# Seeeduino_GPRS_v1_0.net
KiCad netlist of a schematic drawn in EAGLE
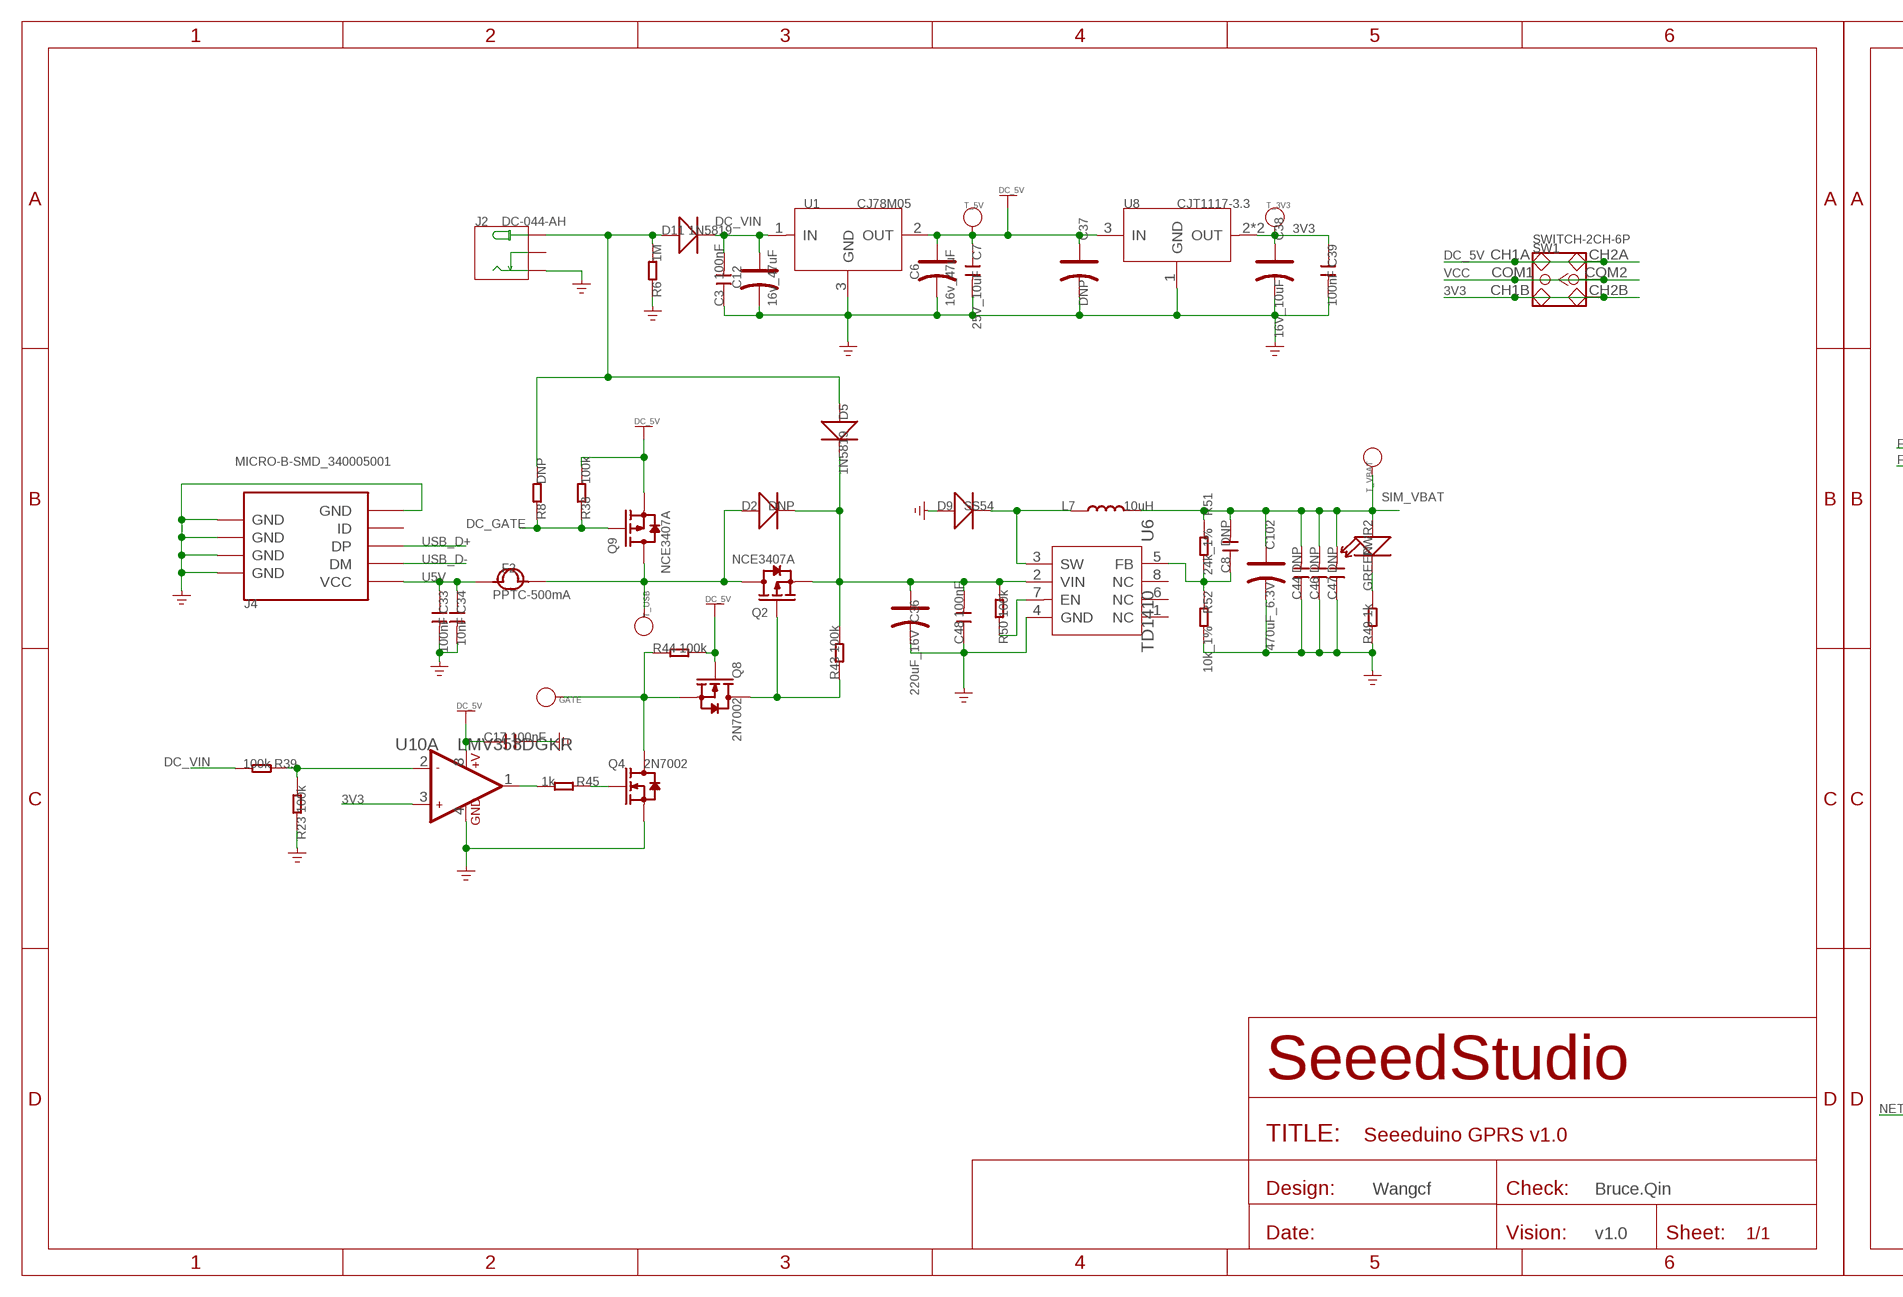
[diagram p0: schematic, sheet 1, part 1 of 3]
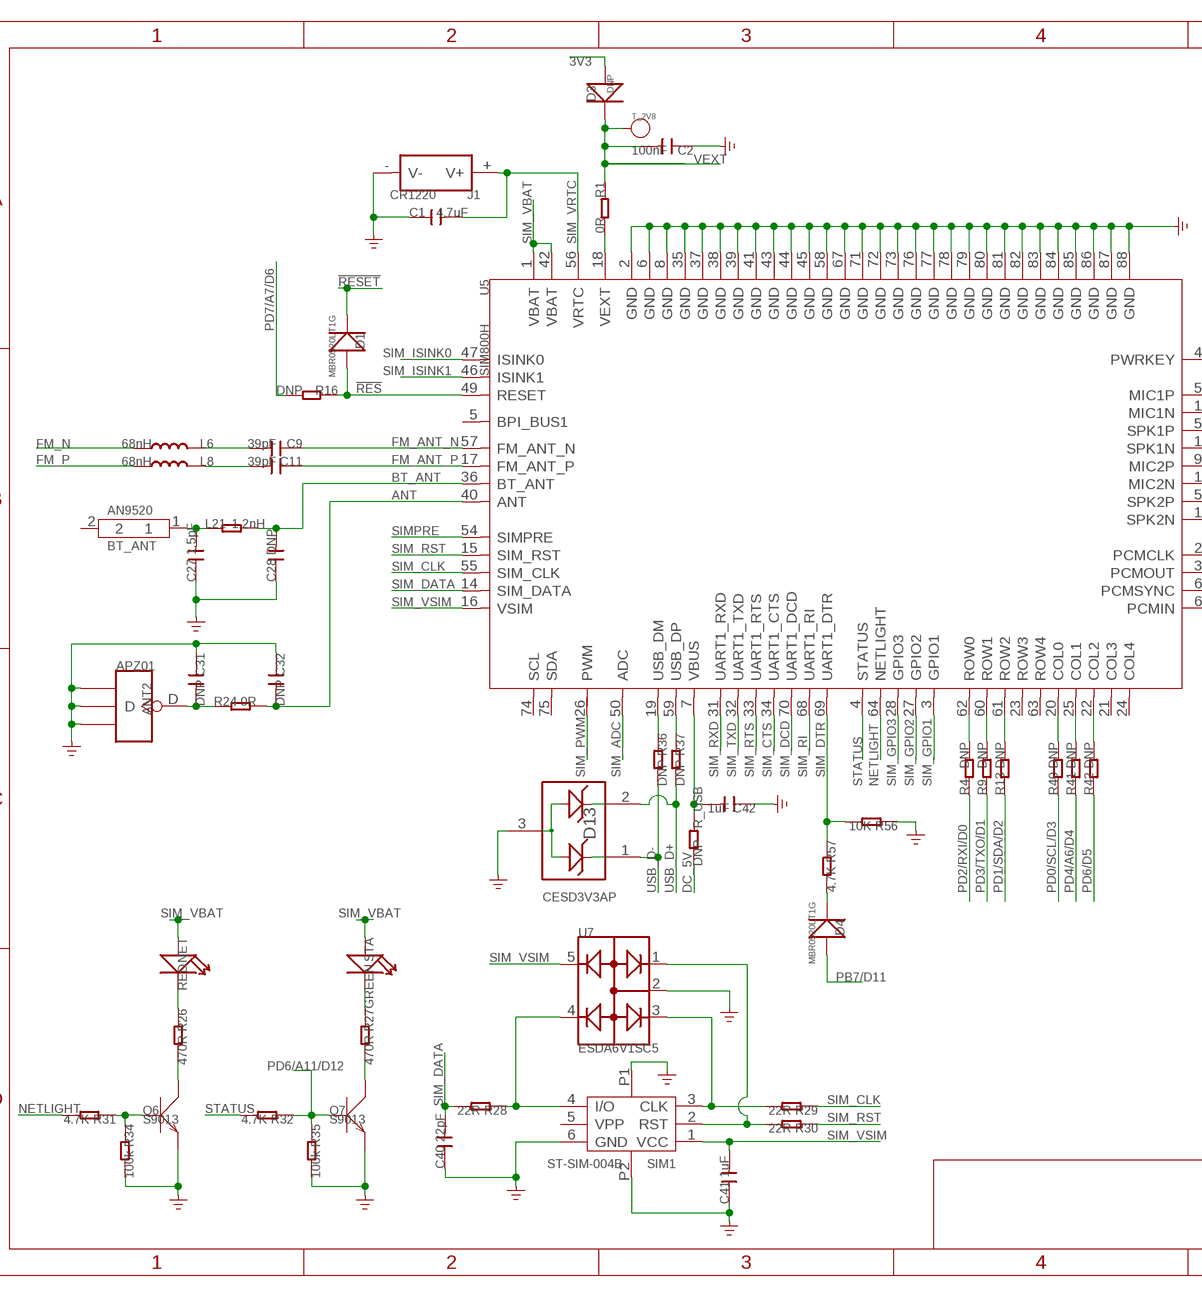
[diagram p1: schematic, sheet 1, part 2 of 3]
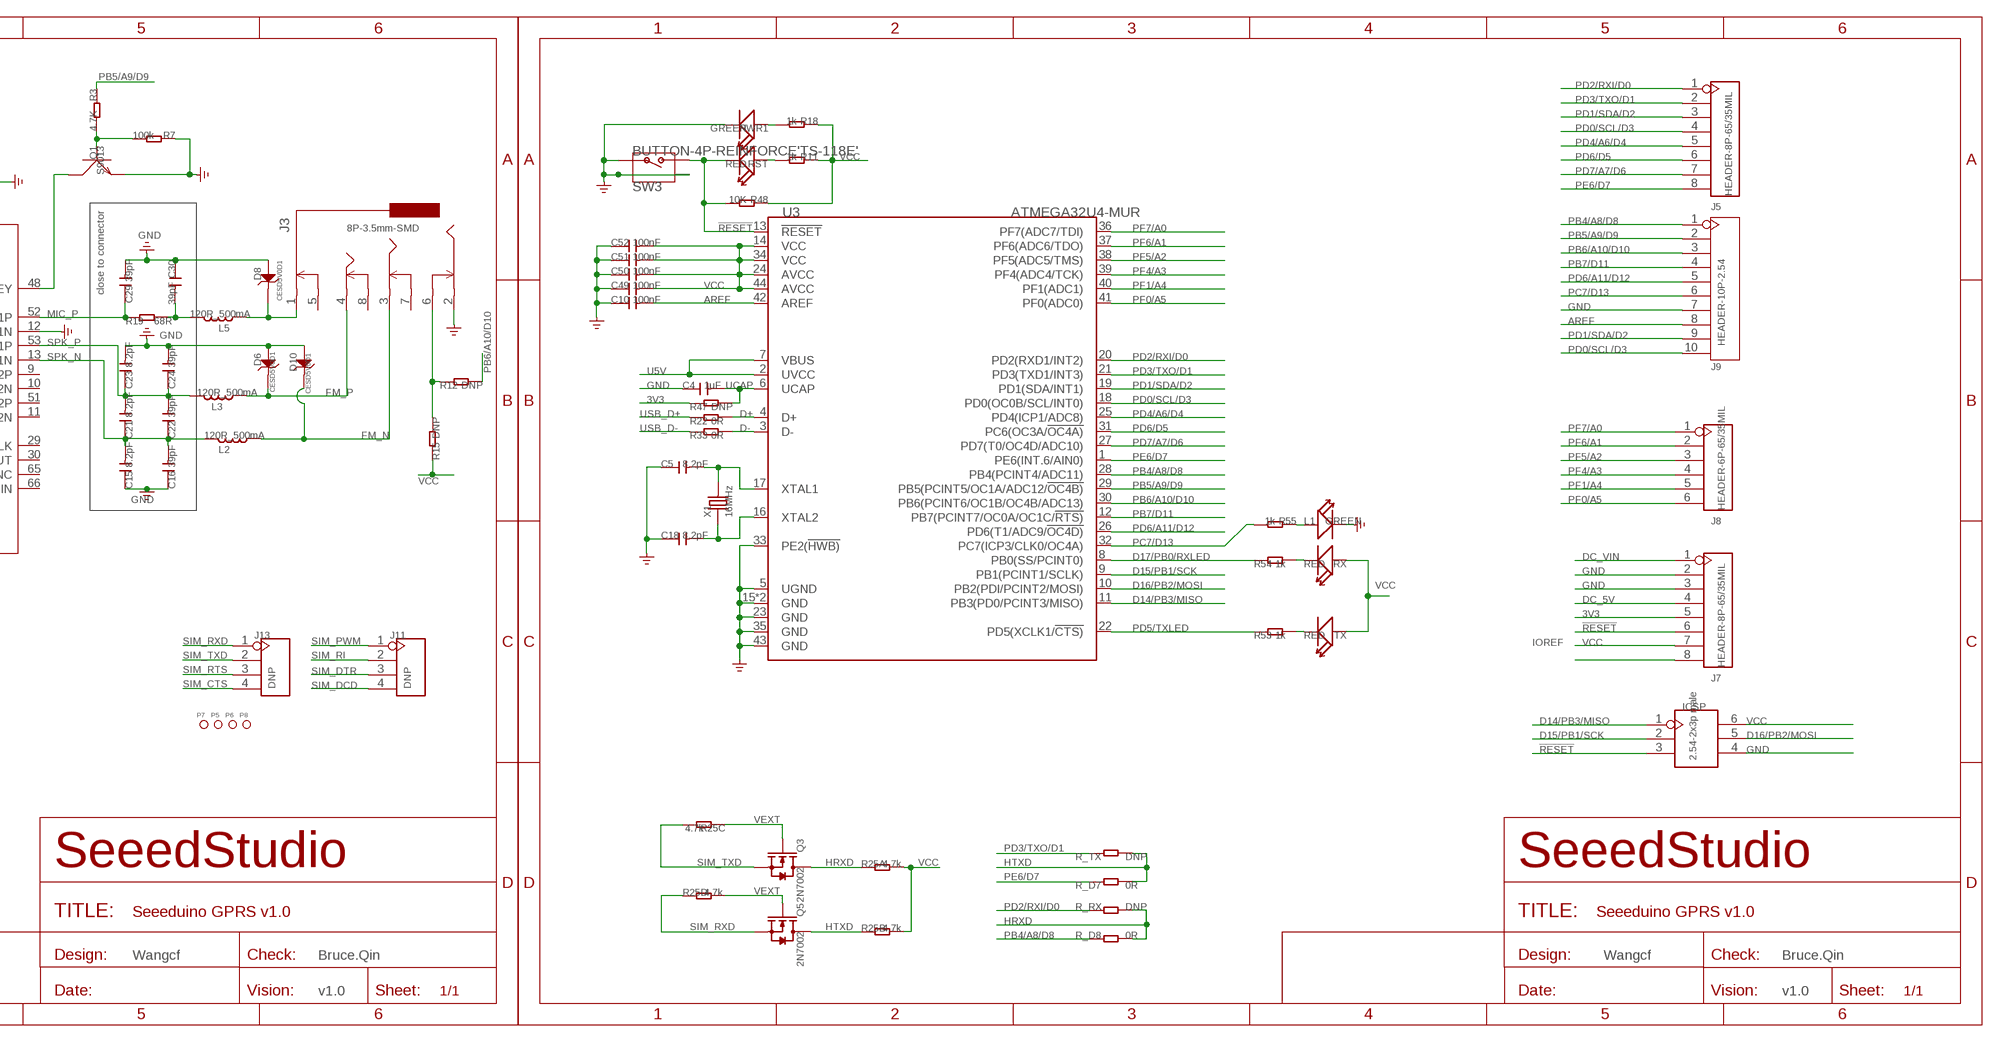
[diagram p2: schematic, sheet 1, part 3 of 3]

(export (version "E")
  (design (tool "Eeschema 10.0.6"))
  (components
    (comp (ref "ANT2")
      (value "APZ01")
      (footprint "eagle-import:4P-U-FL")
      (libsource (lib "eagle-import") (part "ANTENNA-U-FL"))
    )
    (comp (ref "BT_ANT")
      (value "AN9520")
      (footprint "eagle-import:2P-9.5X2.1X1MM")
      (libsource (lib "eagle-import") (part "ANTENNA-CERAMICS'AN9520'"))
    )
    (comp (ref "C1")
      (value "4.7uF")
      (footprint "eagle-import:C0805")
      (libsource (lib "eagle-import") (part "C-0805"))
    )
    (comp (ref "C2")
      (value "100nF")
      (footprint "eagle-import:C0603")
      (libsource (lib "eagle-import") (part "C-0603"))
    )
    (comp (ref "C3")
      (value "100nF")
      (footprint "eagle-import:C0603")
      (libsource (lib "eagle-import") (part "C-0603"))
    )
    (comp (ref "C4")
      (value "1uF")
      (footprint "eagle-import:C0603")
      (libsource (lib "eagle-import") (part "C-0603"))
    )
    (comp (ref "C5")
      (value "8.2pF")
      (footprint "eagle-import:C0603")
      (libsource (lib "eagle-import") (part "C-0603"))
    )
    (comp (ref "C6")
      (value "16v_47uF")
      (footprint "eagle-import:AVX-C")
      (libsource (lib "eagle-import") (part "CAP-AVX-C"))
    )
    (comp (ref "C7")
      (value "25V_10uF")
      (footprint "eagle-import:C0805")
      (libsource (lib "eagle-import") (part "C-0805"))
    )
    (comp (ref "C8")
      (value "DNP")
      (footprint "eagle-import:C0603")
      (libsource (lib "eagle-import") (part "C-0603"))
    )
    (comp (ref "C9")
      (value "39pF")
      (footprint "eagle-import:C0603")
      (libsource (lib "eagle-import") (part "C-0603"))
    )
    (comp (ref "C10")
      (value "100nF")
      (footprint "eagle-import:C0603")
      (libsource (lib "eagle-import") (part "C-0603"))
    )
    (comp (ref "C11")
      (value "39pF")
      (footprint "eagle-import:C0603")
      (libsource (lib "eagle-import") (part "C-0603"))
    )
    (comp (ref "C12")
      (value "16v_47uF")
      (footprint "eagle-import:AVX-C")
      (libsource (lib "eagle-import") (part "CAP-AVX-C"))
    )
    (comp (ref "C15")
      (value "8.2pF")
      (footprint "eagle-import:C0603")
      (libsource (lib "eagle-import") (part "C-0603"))
    )
    (comp (ref "C16")
      (value "39pF")
      (footprint "eagle-import:C0603")
      (libsource (lib "eagle-import") (part "C-0603"))
    )
    (comp (ref "C17")
      (value "100nF")
      (footprint "eagle-import:C0603")
      (libsource (lib "eagle-import") (part "C-0603"))
    )
    (comp (ref "C18")
      (value "8.2pF")
      (footprint "eagle-import:C0603")
      (libsource (lib "eagle-import") (part "C-0603"))
    )
    (comp (ref "C21")
      (value "8.2pF")
      (footprint "eagle-import:C0603")
      (libsource (lib "eagle-import") (part "C-0603"))
    )
    (comp (ref "C22")
      (value "39pF")
      (footprint "eagle-import:C0603")
      (libsource (lib "eagle-import") (part "C-0603"))
    )
    (comp (ref "C23")
      (value "8.2pF")
      (footprint "eagle-import:C0603")
      (libsource (lib "eagle-import") (part "C-0603"))
    )
    (comp (ref "C24")
      (value "39pF")
      (footprint "eagle-import:C0603")
      (libsource (lib "eagle-import") (part "C-0603"))
    )
    (comp (ref "C27")
      (value "1.5pF")
      (footprint "eagle-import:C0603")
      (libsource (lib "eagle-import") (part "C-0603"))
    )
    (comp (ref "C28")
      (value "DNP")
      (footprint "eagle-import:C0603")
      (libsource (lib "eagle-import") (part "C-0603"))
    )
    (comp (ref "C29")
      (value "39pF")
      (footprint "eagle-import:C0603")
      (libsource (lib "eagle-import") (part "C-0603"))
    )
    (comp (ref "C30")
      (value "39pF")
      (footprint "eagle-import:C0603")
      (libsource (lib "eagle-import") (part "C-0603"))
    )
    (comp (ref "C31")
      (value "DNP")
      (footprint "eagle-import:C0603")
      (libsource (lib "eagle-import") (part "C-0603"))
    )
    (comp (ref "C32")
      (value "DNP")
      (footprint "eagle-import:C0603")
      (libsource (lib "eagle-import") (part "C-0603"))
    )
    (comp (ref "C33")
      (value "100nF")
      (footprint "eagle-import:C0603")
      (libsource (lib "eagle-import") (part "C-0603"))
    )
    (comp (ref "C34")
      (value "10nF")
      (footprint "eagle-import:C0603")
      (libsource (lib "eagle-import") (part "C-0603"))
    )
    (comp (ref "C36")
      (value "220uF_16V")
      (footprint "eagle-import:ELECTRO-SMD-D-5.6MM")
      (libsource (lib "eagle-import") (part "CAP-ELECTRO-D"))
    )
    (comp (ref "C37")
      (value "DNP")
      (footprint "eagle-import:AVX-A")
      (libsource (lib "eagle-import") (part "CAP-AVX-A"))
    )
    (comp (ref "C38")
      (value "16V_10uF")
      (footprint "eagle-import:AVX-A")
      (libsource (lib "eagle-import") (part "CAP-AVX-A"))
    )
    (comp (ref "C39")
      (value "100nF")
      (footprint "eagle-import:C0603")
      (libsource (lib "eagle-import") (part "C-0603"))
    )
    (comp (ref "C40")
      (value "22pF")
      (footprint "eagle-import:C0603")
      (libsource (lib "eagle-import") (part "C-0603"))
    )
    (comp (ref "C41")
      (value "1uF")
      (footprint "eagle-import:C0603")
      (libsource (lib "eagle-import") (part "C-0603"))
    )
    (comp (ref "C42")
      (value "1uF")
      (footprint "eagle-import:C0603")
      (libsource (lib "eagle-import") (part "C-0603"))
    )
    (comp (ref "C44")
      (value "DNP")
      (footprint "eagle-import:C0603")
      (libsource (lib "eagle-import") (part "C-0603"))
    )
    (comp (ref "C46")
      (value "DNP")
      (footprint "eagle-import:C0603")
      (libsource (lib "eagle-import") (part "C-0603"))
    )
    (comp (ref "C47")
      (value "DNP")
      (footprint "eagle-import:C0603")
      (libsource (lib "eagle-import") (part "C-0603"))
    )
    (comp (ref "C48")
      (value "100nF")
      (footprint "eagle-import:C0603")
      (libsource (lib "eagle-import") (part "C-0603"))
    )
    (comp (ref "C49")
      (value "100nF")
      (footprint "eagle-import:C0603")
      (libsource (lib "eagle-import") (part "C-0603"))
    )
    (comp (ref "C50")
      (value "100nF")
      (footprint "eagle-import:C0603")
      (libsource (lib "eagle-import") (part "C-0603"))
    )
    (comp (ref "C51")
      (value "100nF")
      (footprint "eagle-import:C0603")
      (libsource (lib "eagle-import") (part "C-0603"))
    )
    (comp (ref "C52")
      (value "100nF")
      (footprint "eagle-import:C0603")
      (libsource (lib "eagle-import") (part "C-0603"))
    )
    (comp (ref "C102")
      (value "470uF_6.3V")
      (footprint "eagle-import:AVX-D")
      (libsource (lib "eagle-import") (part "CAP-AVX-D"))
    )
    (comp (ref "D1")
      (value "MBR0520LT1G")
      (footprint "eagle-import:SOD123")
      (libsource (lib "eagle-import") (part "D'1206'"))
    )
    (comp (ref "D2")
      (value "DNP")
      (footprint "eagle-import:SMA")
      (libsource (lib "eagle-import") (part "D'B130L-13-F'"))
    )
    (comp (ref "D3")
      (value "DNP")
      (footprint "eagle-import:SOD123")
      (libsource (lib "eagle-import") (part "D'1206'"))
    )
    (comp (ref "D4")
      (value "MBR0520LT1G")
      (footprint "eagle-import:SOD123")
      (libsource (lib "eagle-import") (part "D'1206'"))
    )
    (comp (ref "D5")
      (value "1N5819")
      (footprint "eagle-import:SMA")
      (libsource (lib "eagle-import") (part "D'B130L-13-F'"))
    )
    (comp (ref "D6")
      (value "CESD5V0D1")
      (footprint "eagle-import:SOD123-2.7X1.6")
      (libsource (lib "eagle-import") (part "D-ESD"))
    )
    (comp (ref "D8")
      (value "CESD5V0D1")
      (footprint "eagle-import:SOD123-2.7X1.6")
      (libsource (lib "eagle-import") (part "D-ESD"))
    )
    (comp (ref "D9")
      (value "SS54")
      (footprint "eagle-import:SMB")
      (libsource (lib "eagle-import") (part "D'MBRS240LT3'"))
    )
    (comp (ref "D10")
      (value "CESD5V0D1")
      (footprint "eagle-import:SOD123-2.7X1.6")
      (libsource (lib "eagle-import") (part "D-ESD"))
    )
    (comp (ref "D11")
      (value "1N5819")
      (footprint "eagle-import:SMA")
      (libsource (lib "eagle-import") (part "D'B130L-13-F'"))
    )
    (comp (ref "D13")
      (value "CESD3V3AP")
      (footprint "eagle-import:SOT23")
      (libsource (lib "eagle-import") (part "D-ESD-3P"))
    )
    (comp (ref "F2")
      (value "PPTC-500mA")
      (footprint "eagle-import:1206")
      (libsource (lib "eagle-import") (part "FUSE"))
    )
    (comp (ref "GATE")
      (value "DNP")
      (footprint "eagle-import:TP_4545")
      (libsource (lib "eagle-import") (part "PAD-TEST-POINT-CIRCLE'4545'"))
    )
    (comp (ref "ICSP")
      (value "2.54-2x3p male")
      (footprint "eagle-import:2X3P-2.54")
      (libsource (lib "eagle-import") (part "HEADER-2X3P-2.54"))
    )
    (comp (ref "J1")
      (value "CR1220")
      (footprint "eagle-import:SMD-CR1220-2")
      (libsource (lib "eagle-import") (part "HOLDER-BAT"))
    )
    (comp (ref "J2")
      (value "DC-044-AH")
      (footprint "eagle-import:DC-404")
      (libsource (lib "eagle-import") (part "DC-044"))
    )
    (comp (ref "J3")
      (value "8P-3.5mm-SMD")
      (footprint "eagle-import:8P-3.5-SMD")
      (libsource (lib "eagle-import") (part "AUDIO-8P'PJ-3536-L6S'"))
    )
    (comp (ref "J4")
      (value "MICRO-B-SMD_340005001")
      (footprint "eagle-import:MICRO-USB")
      (libsource (lib "eagle-import") (part "USB-MINIUSB-5P-MICRO"))
    )
    (comp (ref "J5")
      (value "HEADER-8P-65/35MIL")
      (footprint "eagle-import:8P-2.54-65_35MIL")
      (libsource (lib "eagle-import") (part "HEADER-8P-65/35MIL"))
    )
    (comp (ref "J7")
      (value "HEADER-8P-65/35MIL")
      (footprint "eagle-import:8P-2.54-65_35MIL")
      (libsource (lib "eagle-import") (part "HEADER-8P-65/35MIL"))
    )
    (comp (ref "J8")
      (value "HEADER-6P-65/35MIL")
      (footprint "eagle-import:6P-2.54-65_35MIL")
      (libsource (lib "eagle-import") (part "HEADER-6P-65/35MIL"))
    )
    (comp (ref "J9")
      (value "HEADER-10P-2.54")
      (footprint "eagle-import:10P-2.54")
      (libsource (lib "eagle-import") (part "HEADER-10P-2.54"))
    )
    (comp (ref "J11")
      (value "DNP")
      (footprint "eagle-import:4P-65_35MIL")
      (libsource (lib "eagle-import") (part "HEADER-4P-65/35MIL"))
    )
    (comp (ref "J13")
      (value "DNP")
      (footprint "eagle-import:4P-65_35MIL")
      (libsource (lib "eagle-import") (part "HEADER-4P-65/35MIL"))
    )
    (comp (ref "L1")
      (value "GREEN")
      (footprint "eagle-import:LED-0603")
      (libsource (lib "eagle-import") (part "LED'0603'"))
    )
    (comp (ref "L2")
      (value "120R_500mA")
      (footprint "eagle-import:L0603")
      (libsource (lib "eagle-import") (part "L'0603'"))
    )
    (comp (ref "L3")
      (value "120R_500mA")
      (footprint "eagle-import:L0603")
      (libsource (lib "eagle-import") (part "L'0603'"))
    )
    (comp (ref "L5")
      (value "120R_500mA")
      (footprint "eagle-import:L0603")
      (libsource (lib "eagle-import") (part "L'0603'"))
    )
    (comp (ref "L6")
      (value "68nH")
      (footprint "eagle-import:L0603")
      (libsource (lib "eagle-import") (part "L'0603'"))
    )
    (comp (ref "L7")
      (value "10uH")
      (footprint "eagle-import:L0630")
      (libsource (lib "eagle-import") (part "L'0630'"))
    )
    (comp (ref "L8")
      (value "68nH")
      (footprint "eagle-import:L0603")
      (libsource (lib "eagle-import") (part "L'0603'"))
    )
    (comp (ref "L21")
      (value "1.2nH")
      (footprint "eagle-import:R0603")
      (libsource (lib "eagle-import") (part "R-0603"))
    )
    (comp (ref "NET")
      (value "RED")
      (footprint "eagle-import:LED-0603")
      (libsource (lib "eagle-import") (part "LED'0603'"))
    )
    (comp (ref "P5")
      (value "DNP")
      (footprint "eagle-import:ROUND-MARK-1.0")
      (libsource (lib "eagle-import") (part "PAD-MARK"))
    )
    (comp (ref "P6")
      (value "DNP")
      (footprint "eagle-import:ROUND-MARK-1.0")
      (libsource (lib "eagle-import") (part "PAD-MARK"))
    )
    (comp (ref "P7")
      (value "DNP")
      (footprint "eagle-import:ROUND-MARK-1.0")
      (libsource (lib "eagle-import") (part "PAD-MARK"))
    )
    (comp (ref "P8")
      (value "DNP")
      (footprint "eagle-import:ROUND-MARK-1.0")
      (libsource (lib "eagle-import") (part "PAD-MARK"))
    )
    (comp (ref "PWR1")
      (value "GREEN")
      (footprint "eagle-import:LED-0603")
      (libsource (lib "eagle-import") (part "LED'0603'"))
    )
    (comp (ref "PWR2")
      (value "GREEN")
      (footprint "eagle-import:LED-0603")
      (libsource (lib "eagle-import") (part "LED'0603'"))
    )
    (comp (ref "Q1")
      (value "S9013")
      (footprint "eagle-import:SOT23")
      (libsource (lib "eagle-import") (part "TRANSISTOR-NPN-SOT23"))
    )
    (comp (ref "Q2")
      (value "NCE3407A")
      (footprint "eagle-import:SOT23")
      (libsource (lib "eagle-import") (part "MOSFET-P'SI2323CDS/SI2305DS{lt}BR{gt}'"))
    )
    (comp (ref "Q3")
      (value "2N7002")
      (footprint "eagle-import:SOT23")
      (libsource (lib "eagle-import") (part "MOSFET-N'SOT23'"))
    )
    (comp (ref "Q4")
      (value "2N7002")
      (footprint "eagle-import:SOT23")
      (libsource (lib "eagle-import") (part "MOSFET-N'SOT23'"))
    )
    (comp (ref "Q5")
      (value "2N7002")
      (footprint "eagle-import:SOT23")
      (libsource (lib "eagle-import") (part "MOSFET-N'SOT23'"))
    )
    (comp (ref "Q6")
      (value "S9013")
      (footprint "eagle-import:SOT23")
      (libsource (lib "eagle-import") (part "TRANSISTOR-NPN-SOT23"))
    )
    (comp (ref "Q7")
      (value "S9013")
      (footprint "eagle-import:SOT23")
      (libsource (lib "eagle-import") (part "TRANSISTOR-NPN-SOT23"))
    )
    (comp (ref "Q8")
      (value "2N7002")
      (footprint "eagle-import:SOT23")
      (libsource (lib "eagle-import") (part "MOSFET-N'SOT23'"))
    )
    (comp (ref "Q9")
      (value "NCE3407A")
      (footprint "eagle-import:SOT23")
      (libsource (lib "eagle-import") (part "MOSFET-P'SI2323CDS/SI2305DS{lt}BR{gt}'"))
    )
    (comp (ref "R1")
      (value "0R")
      (footprint "eagle-import:R0603")
      (libsource (lib "eagle-import") (part "R-0603"))
    )
    (comp (ref "R3")
      (value "4.7K")
      (footprint "eagle-import:R0603")
      (libsource (lib "eagle-import") (part "R-0603"))
    )
    (comp (ref "R4")
      (value "DNP")
      (footprint "eagle-import:R0603")
      (libsource (lib "eagle-import") (part "R-0603"))
    )
    (comp (ref "R6")
      (value "1M")
      (footprint "eagle-import:R0603")
      (libsource (lib "eagle-import") (part "R-0603"))
    )
    (comp (ref "R7")
      (value "100k")
      (footprint "eagle-import:R0603")
      (libsource (lib "eagle-import") (part "R-0603"))
    )
    (comp (ref "R8")
      (value "DNP")
      (footprint "eagle-import:R0603")
      (libsource (lib "eagle-import") (part "R-0603"))
    )
    (comp (ref "R9")
      (value "DNP")
      (footprint "eagle-import:R0603")
      (libsource (lib "eagle-import") (part "R-0603"))
    )
    (comp (ref "R11")
      (value "1k")
      (footprint "eagle-import:R0603")
      (libsource (lib "eagle-import") (part "R-0603"))
    )
    (comp (ref "R12")
      (value "DNP")
      (footprint "eagle-import:R0603")
      (libsource (lib "eagle-import") (part "R-0603"))
    )
    (comp (ref "R13")
      (value "DNP")
      (footprint "eagle-import:R0603")
      (libsource (lib "eagle-import") (part "R-0603"))
    )
    (comp (ref "R15")
      (value "DNP")
      (footprint "eagle-import:R0603")
      (libsource (lib "eagle-import") (part "R-0603"))
    )
    (comp (ref "R16")
      (value "DNP")
      (footprint "eagle-import:R0603")
      (libsource (lib "eagle-import") (part "R-0603"))
    )
    (comp (ref "R18")
      (value "1k")
      (footprint "eagle-import:R0603")
      (libsource (lib "eagle-import") (part "R-0603"))
    )
    (comp (ref "R19")
      (value "68R")
      (footprint "eagle-import:R0603")
      (libsource (lib "eagle-import") (part "R-0603"))
    )
    (comp (ref "R22")
      (value "0R")
      (footprint "eagle-import:R0603")
      (libsource (lib "eagle-import") (part "R-0603"))
    )
    (comp (ref "R23")
      (value "100k")
      (footprint "eagle-import:R0603")
      (libsource (lib "eagle-import") (part "R-0603"))
    )
    (comp (ref "R24")
      (value "0R")
      (footprint "eagle-import:R0603")
      (libsource (lib "eagle-import") (part "R-0603"))
    )
    (comp (ref "R25")
      (value "4.7k")
      (footprint "eagle-import:1206-8-3.3X2.4")
      (libsource (lib "eagle-import") (part "R-4R-1206"))
    )
    (comp (ref "R26")
      (value "470R")
      (footprint "eagle-import:R0603")
      (libsource (lib "eagle-import") (part "R-0603"))
    )
    (comp (ref "R27")
      (value "470R")
      (footprint "eagle-import:R0603")
      (libsource (lib "eagle-import") (part "R-0603"))
    )
    (comp (ref "R28")
      (value "22R")
      (footprint "eagle-import:R0603")
      (libsource (lib "eagle-import") (part "R-0603"))
    )
    (comp (ref "R29")
      (value "22R")
      (footprint "eagle-import:R0603")
      (libsource (lib "eagle-import") (part "R-0603"))
    )
    (comp (ref "R30")
      (value "22R")
      (footprint "eagle-import:R0603")
      (libsource (lib "eagle-import") (part "R-0603"))
    )
    (comp (ref "R31")
      (value "4.7K")
      (footprint "eagle-import:R0603")
      (libsource (lib "eagle-import") (part "R-0603"))
    )
    (comp (ref "R32")
      (value "4.7K")
      (footprint "eagle-import:R0603")
      (libsource (lib "eagle-import") (part "R-0603"))
    )
    (comp (ref "R33")
      (value "0R")
      (footprint "eagle-import:R0603")
      (libsource (lib "eagle-import") (part "R-0603"))
    )
    (comp (ref "R34")
      (value "100k")
      (footprint "eagle-import:R0603")
      (libsource (lib "eagle-import") (part "R-0603"))
    )
    (comp (ref "R35")
      (value "100k")
      (footprint "eagle-import:R0603")
      (libsource (lib "eagle-import") (part "R-0603"))
    )
    (comp (ref "R36")
      (value "DNP")
      (footprint "eagle-import:R0603")
      (libsource (lib "eagle-import") (part "R-0603"))
    )
    (comp (ref "R37")
      (value "DNP")
      (footprint "eagle-import:R0603")
      (libsource (lib "eagle-import") (part "R-0603"))
    )
    (comp (ref "R38")
      (value "100k")
      (footprint "eagle-import:R0603")
      (libsource (lib "eagle-import") (part "R-0603"))
    )
    (comp (ref "R39")
      (value "100k")
      (footprint "eagle-import:R0603")
      (libsource (lib "eagle-import") (part "R-0603"))
    )
    (comp (ref "R40")
      (value "DNP")
      (footprint "eagle-import:R0603")
      (libsource (lib "eagle-import") (part "R-0603"))
    )
    (comp (ref "R41")
      (value "DNP")
      (footprint "eagle-import:R0603")
      (libsource (lib "eagle-import") (part "R-0603"))
    )
    (comp (ref "R42")
      (value "DNP")
      (footprint "eagle-import:R0603")
      (libsource (lib "eagle-import") (part "R-0603"))
    )
    (comp (ref "R43")
      (value "100k")
      (footprint "eagle-import:R0603")
      (libsource (lib "eagle-import") (part "R-0603"))
    )
    (comp (ref "R44")
      (value "100k")
      (footprint "eagle-import:R0603")
      (libsource (lib "eagle-import") (part "R-0603"))
    )
    (comp (ref "R45")
      (value "1k")
      (footprint "eagle-import:R0603")
      (libsource (lib "eagle-import") (part "R-0603"))
    )
    (comp (ref "R47")
      (value "DNP")
      (footprint "eagle-import:R0603")
      (libsource (lib "eagle-import") (part "R-0603"))
    )
    (comp (ref "R48")
      (value "10K")
      (footprint "eagle-import:R0603")
      (libsource (lib "eagle-import") (part "R-0603"))
    )
    (comp (ref "R49")
      (value "1k")
      (footprint "eagle-import:R0603")
      (libsource (lib "eagle-import") (part "R-0603"))
    )
    (comp (ref "R50")
      (value "100k")
      (footprint "eagle-import:R0603")
      (libsource (lib "eagle-import") (part "R-0603"))
    )
    (comp (ref "R51")
      (value "24k_1%")
      (footprint "eagle-import:R0603")
      (libsource (lib "eagle-import") (part "R-0603"))
    )
    (comp (ref "R52")
      (value "10k_1%")
      (footprint "eagle-import:R0603")
      (libsource (lib "eagle-import") (part "R-0603"))
    )
    (comp (ref "R53")
      (value "1k")
      (footprint "eagle-import:R0603")
      (libsource (lib "eagle-import") (part "R-0603"))
    )
    (comp (ref "R54")
      (value "1k")
      (footprint "eagle-import:R0603")
      (libsource (lib "eagle-import") (part "R-0603"))
    )
    (comp (ref "R55")
      (value "1k")
      (footprint "eagle-import:R0603")
      (libsource (lib "eagle-import") (part "R-0603"))
    )
    (comp (ref "R56")
      (value "10K")
      (footprint "eagle-import:R0603")
      (libsource (lib "eagle-import") (part "R-0603"))
    )
    (comp (ref "R57")
      (value "4.7K")
      (footprint "eagle-import:R0603")
      (libsource (lib "eagle-import") (part "R-0603"))
    )
    (comp (ref "RST")
      (value "RED")
      (footprint "eagle-import:LED-0603")
      (libsource (lib "eagle-import") (part "LED'0603'"))
    )
    (comp (ref "RX")
      (value "RED")
      (footprint "eagle-import:LED-0603")
      (libsource (lib "eagle-import") (part "LED'0603'"))
    )
    (comp (ref "R_D7")
      (value "0R")
      (footprint "eagle-import:R0603")
      (libsource (lib "eagle-import") (part "R-0603"))
    )
    (comp (ref "R_D8")
      (value "0R")
      (footprint "eagle-import:R0603")
      (libsource (lib "eagle-import") (part "R-0603"))
    )
    (comp (ref "R_RX")
      (value "DNP")
      (footprint "eagle-import:R0603")
      (libsource (lib "eagle-import") (part "R-0603"))
    )
    (comp (ref "R_TX")
      (value "DNP")
      (footprint "eagle-import:R0603")
      (libsource (lib "eagle-import") (part "R-0603"))
    )
    (comp (ref "R_USB")
      (value "DNP")
      (footprint "eagle-import:R0603")
      (libsource (lib "eagle-import") (part "R-0603"))
    )
    (comp (ref "SIM1")
      (value "ST-SIM-004B")
      (footprint "eagle-import:6P-1.8")
      (libsource (lib "eagle-import") (part "SIM-CARD'ST-SIM-004B'"))
    )
    (comp (ref "STA")
      (value "GREEN")
      (footprint "eagle-import:LED-0603")
      (libsource (lib "eagle-import") (part "LED'0603'"))
    )
    (comp (ref "SW1")
      (value "SWITCH-2CH-6P")
      (footprint "eagle-import:6P-2CH-2.5-9.1X3.5X3.2H")
      (libsource (lib "eagle-import") (part "SWITCH-2CH-6P'MS-22D18'"))
    )
    (comp (ref "SW3")
      (value "BUTTON-4P-REINFORCE'TS-118E'")
      (footprint "eagle-import:4P-SMD-7X3.5X3.5H")
      (libsource (lib "eagle-import") (part "BUTTON-4P-REINFORCE'TS-118E'"))
    )
    (comp (ref "TX")
      (value "RED")
      (footprint "eagle-import:LED-0603")
      (libsource (lib "eagle-import") (part "LED'0603'"))
    )
    (comp (ref "T_2V8")
      (value "DNP")
      (footprint "eagle-import:TP_4545")
      (libsource (lib "eagle-import") (part "PAD-TEST-POINT-CIRCLE'4545'"))
    )
    (comp (ref "T_3V3")
      (value "DNP")
      (footprint "eagle-import:TP_4545")
      (libsource (lib "eagle-import") (part "PAD-TEST-POINT-CIRCLE'4545'"))
    )
    (comp (ref "T_5V")
      (value "DNP")
      (footprint "eagle-import:TP_4545")
      (libsource (lib "eagle-import") (part "PAD-TEST-POINT-CIRCLE'4545'"))
    )
    (comp (ref "T_USB")
      (value "DNP")
      (footprint "eagle-import:TP_4545")
      (libsource (lib "eagle-import") (part "PAD-TEST-POINT-CIRCLE'4545'"))
    )
    (comp (ref "T_VBAT")
      (value "DNP")
      (footprint "eagle-import:TP_4545")
      (libsource (lib "eagle-import") (part "PAD-TEST-POINT-CIRCLE'4545'"))
    )
    (comp (ref "U1")
      (value "CJ78M05")
      (footprint "eagle-import:TO252")
      (libsource (lib "eagle-import") (part "78M05-TO252"))
    )
    (comp (ref "U3")
      (value "ATMEGA32U4-MUR")
      (footprint "eagle-import:QFN44")
      (libsource (lib "eagle-import") (part "ATMEGA32U4-MU"))
    )
    (comp (ref "U5")
      (value "SIM800H")
      (footprint "eagle-import:88P-17.8X15.8X2.4H")
      (libsource (lib "eagle-import") (part "SIM800H"))
    )
    (comp (ref "U6")
      (value "TD1410")
      (footprint "eagle-import:SOP8")
      (libsource (lib "eagle-import") (part "TD1410"))
    )
    (comp (ref "U7")
      (value "ESDA6V1SC5")
      (footprint "eagle-import:SOT23-5L")
      (libsource (lib "eagle-import") (part "D-ESD-ESDA6V1SC5-SOT23-5L"))
    )
    (comp (ref "U8")
      (value "CJT1117-3.3")
      (footprint "eagle-import:SOT-223")
      (libsource (lib "eagle-import") (part "LD1117S"))
    )
    (comp (ref "U10")
      (value "LMV358DGKR")
      (footprint "eagle-import:MSOP8")
      (libsource (lib "eagle-import") (part "LMV358DGK"))
    )
    (comp (ref "X1")
      (value "16MHz")
      (footprint "eagle-import:2P-SMD-5X3.2")
      (libsource (lib "eagle-import") (part "CRYSTAL'5032'"))
    )
  )
  (nets
    (net (code "1") (name "/3V3") (class "Default")
      (node (ref "C38") (pin "+") (pinfunction "+_+") (pintype "passive"))
      (node (ref "C39") (pin "1") (pinfunction "1_1") (pintype "passive"))
      (node (ref "D3") (pin "+") (pinfunction "+_+") (pintype "passive"))
      (node (ref "J7") (pin "5") (pinfunction "5_5") (pintype "bidirectional"))
      (node (ref "R47") (pin "1") (pinfunction "1_1") (pintype "passive"))
      (node (ref "SW1") (pin "CH1B") (pinfunction "CH1B_CH1B") (pintype "bidirectional"))
      (node (ref "SW1") (pin "CH2B") (pinfunction "CH2B_CH2B") (pintype "bidirectional"))
      (node (ref "T_3V3") (pin "T") (pinfunction "T_T") (pintype "bidirectional"))
      (node (ref "U10") (pin "3") (pinfunction "+IN1_3") (pintype "input"))
      (node (ref "U8") (pin "2") (pinfunction "OUT_2") (pintype "bidirectional"))
      (node (ref "U8") (pin "TER") (pinfunction "OUT_TER") (pintype "bidirectional"))
    )
    (net (code "2") (name "/ANT") (class "Default")
      (node (ref "C32") (pin "2") (pinfunction "2_2") (pintype "passive"))
      (node (ref "R24") (pin "2") (pinfunction "2_2") (pintype "passive"))
      (node (ref "U5") (pin "40") (pinfunction "ANT_40") (pintype "bidirectional"))
    )
    (net (code "3") (name "/AREF") (class "Default")
      (node (ref "C10") (pin "2") (pinfunction "2_2") (pintype "passive"))
      (node (ref "J9") (pin "8") (pinfunction "8_8") (pintype "bidirectional"))
      (node (ref "U3") (pin "42") (pinfunction "AREF_42") (pintype "bidirectional"))
    )
    (net (code "4") (name "/BT_ANT") (class "Default")
      (node (ref "C28") (pin "2") (pinfunction "2_2") (pintype "passive"))
      (node (ref "L21") (pin "2") (pinfunction "2_2") (pintype "passive"))
      (node (ref "U5") (pin "36") (pinfunction "BT_ANT_36") (pintype "bidirectional"))
    )
    (net (code "5") (name "/D+") (class "Default")
      (node (ref "R22") (pin "2") (pinfunction "2_2") (pintype "passive"))
      (node (ref "U3") (pin "4") (pinfunction "D+_4") (pintype "bidirectional"))
    )
    (net (code "6") (name "/D-") (class "Default")
      (node (ref "R33") (pin "2") (pinfunction "2_2") (pintype "passive"))
      (node (ref "U3") (pin "3") (pinfunction "D-_3") (pintype "bidirectional"))
    )
    (net (code "7") (name "/D14{slash}PB3{slash}MISO") (class "Default")
      (node (ref "ICSP") (pin "1") (pinfunction "1_1") (pintype "bidirectional"))
      (node (ref "U3") (pin "11") (pinfunction "PB3(PD0/PCINT3/MISO)_11") (pintype "bidirectional"))
    )
    (net (code "8") (name "/D15{slash}PB1{slash}SCK") (class "Default")
      (node (ref "ICSP") (pin "2") (pinfunction "2_2") (pintype "bidirectional"))
      (node (ref "U3") (pin "9") (pinfunction "PB1(PCINT1/SCLK)_9") (pintype "bidirectional"))
    )
    (net (code "9") (name "/D16{slash}PB2{slash}MOSI") (class "Default")
      (node (ref "ICSP") (pin "5") (pinfunction "5_5") (pintype "bidirectional"))
      (node (ref "U3") (pin "10") (pinfunction "PB2(PDI/PCINT2/MOSI)_10") (pintype "bidirectional"))
    )
    (net (code "10") (name "/D17{slash}PB0{slash}RXLED") (class "Default")
      (node (ref "R54") (pin "1") (pinfunction "1_1") (pintype "passive"))
      (node (ref "U3") (pin "8") (pinfunction "PB0(SS/PCINT0)_8") (pintype "bidirectional"))
    )
    (net (code "11") (name "/DC_GATE") (class "Default")
      (node (ref "GATE") (pin "T") (pinfunction "T_T") (pintype "bidirectional"))
      (node (ref "Q4") (pin "3") (pinfunction "D_3") (pintype "passive"))
      (node (ref "Q8") (pin "2") (pinfunction "S_2") (pintype "passive"))
      (node (ref "Q9") (pin "1") (pinfunction "G_1") (pintype "passive"))
      (node (ref "R38") (pin "1") (pinfunction "1_1") (pintype "passive"))
      (node (ref "R44") (pin "1") (pinfunction "1_1") (pintype "passive"))
      (node (ref "R8") (pin "1") (pinfunction "1_1") (pintype "passive"))
    )
    (net (code "12") (name "/DC_VIN") (class "Default")
      (node (ref "C12") (pin "+") (pinfunction "+_+") (pintype "passive"))
      (node (ref "C3") (pin "2") (pinfunction "2_2") (pintype "passive"))
      (node (ref "D11") (pin "1") (pinfunction "-_1") (pintype "passive"))
      (node (ref "J7") (pin "1") (pinfunction "1_1") (pintype "bidirectional"))
      (node (ref "R39") (pin "2") (pinfunction "2_2") (pintype "passive"))
      (node (ref "U1") (pin "1") (pinfunction "IN_1") (pintype "bidirectional"))
    )
    (net (code "13") (name "/FM_ANT_N") (class "Default")
      (node (ref "C9") (pin "1") (pinfunction "1_1") (pintype "passive"))
      (node (ref "U5") (pin "57") (pinfunction "FM_ANT_N_57") (pintype "bidirectional"))
    )
    (net (code "14") (name "/FM_ANT_P") (class "Default")
      (node (ref "C11") (pin "1") (pinfunction "1_1") (pintype "passive"))
      (node (ref "U5") (pin "17") (pinfunction "FM_ANT_P_17") (pintype "bidirectional"))
    )
    (net (code "15") (name "/FM_N") (class "Default")
      (node (ref "D10") (pin "2") (pinfunction "2_2") (pintype "bidirectional"))
      (node (ref "J3") (pin "3") (pinfunction "3_3") (pintype "bidirectional"))
      (node (ref "L2") (pin "2") (pinfunction "2_2") (pintype "passive"))
      (node (ref "L6") (pin "2") (pinfunction "2_2") (pintype "passive"))
    )
    (net (code "16") (name "/FM_P") (class "Default")
      (node (ref "D6") (pin "2") (pinfunction "2_2") (pintype "bidirectional"))
      (node (ref "J3") (pin "4") (pinfunction "4_4") (pintype "bidirectional"))
      (node (ref "L3") (pin "2") (pinfunction "2_2") (pintype "passive"))
      (node (ref "L8") (pin "2") (pinfunction "2_2") (pintype "passive"))
    )
    (net (code "17") (name "/HRXD") (class "Default")
      (node (ref "Q3") (pin "3") (pinfunction "D_3") (pintype "passive"))
      (node (ref "R25") (pin "1") (pinfunction "1_1") (pintype "passive"))
      (node (ref "R_D8") (pin "2") (pinfunction "2_2") (pintype "passive"))
      (node (ref "R_RX") (pin "2") (pinfunction "2_2") (pintype "passive"))
    )
    (net (code "18") (name "/HTXD") (class "Default")
      (node (ref "Q5") (pin "3") (pinfunction "D_3") (pintype "passive"))
      (node (ref "R25") (pin "2") (pinfunction "1_2") (pintype "passive"))
      (node (ref "R_D7") (pin "2") (pinfunction "2_2") (pintype "passive"))
      (node (ref "R_TX") (pin "2") (pinfunction "2_2") (pintype "passive"))
    )
    (net (code "19") (name "/MIC_P") (class "Default")
      (node (ref "C29") (pin "1") (pinfunction "1_1") (pintype "passive"))
      (node (ref "R19") (pin "1") (pinfunction "1_1") (pintype "passive"))
      (node (ref "U5") (pin "52") (pinfunction "MIC1P_52") (pintype "bidirectional"))
    )
    (net (code "20") (name "/NETLIGHT") (class "Default")
      (node (ref "R31") (pin "2") (pinfunction "2_2") (pintype "passive"))
      (node (ref "U5") (pin "64") (pinfunction "NETLIGHT_64") (pintype "bidirectional"))
    )
    (net (code "21") (name "/PB4{slash}A8{slash}D8") (class "Default")
      (node (ref "J9") (pin "1") (pinfunction "1_1") (pintype "bidirectional"))
      (node (ref "R_D8") (pin "1") (pinfunction "1_1") (pintype "passive"))
      (node (ref "U3") (pin "28") (pinfunction "PB4(PCINT4/ADC11)_28") (pintype "bidirectional"))
    )
    (net (code "22") (name "/PB5{slash}A9{slash}D9") (class "Default")
      (node (ref "J9") (pin "2") (pinfunction "2_2") (pintype "bidirectional"))
      (node (ref "R3") (pin "1") (pinfunction "1_1") (pintype "passive"))
      (node (ref "U3") (pin "29") (pinfunction "PB5(PCINT5/OC1A/ADC12/~{OC4B})_29") (pintype "bidirectional"))
    )
    (net (code "23") (name "/PB6{slash}A10{slash}D10") (class "Default")
      (node (ref "J9") (pin "3") (pinfunction "3_3") (pintype "bidirectional"))
      (node (ref "R12") (pin "2") (pinfunction "2_2") (pintype "passive"))
      (node (ref "U3") (pin "30") (pinfunction "PB6(PCINT6/OC1B/OC4B/ADC13)_30") (pintype "bidirectional"))
    )
    (net (code "24") (name "/PB7{slash}D11") (class "Default")
      (node (ref "D4") (pin "+") (pinfunction "+_+") (pintype "passive"))
      (node (ref "J9") (pin "4") (pinfunction "4_4") (pintype "bidirectional"))
      (node (ref "U3") (pin "12") (pinfunction "PB7(PCINT7/OC0A/OC1C/~{RTS})_12") (pintype "bidirectional"))
    )
    (net (code "25") (name "/PC7{slash}D13") (class "Default")
      (node (ref "J9") (pin "6") (pinfunction "6_6") (pintype "bidirectional"))
      (node (ref "R55") (pin "2") (pinfunction "2_2") (pintype "passive"))
      (node (ref "U3") (pin "32") (pinfunction "PC7(ICP3/CLK0/OC4A)_32") (pintype "bidirectional"))
    )
    (net (code "26") (name "/PD0{slash}SCL{slash}D3") (class "Default")
      (node (ref "J5") (pin "4") (pinfunction "4_4") (pintype "bidirectional"))
      (node (ref "J9") (pin "10") (pinfunction "10_10") (pintype "bidirectional"))
      (node (ref "R40") (pin "1") (pinfunction "1_1") (pintype "passive"))
      (node (ref "U3") (pin "18") (pinfunction "PD0(OC0B/SCL/INT0)_18") (pintype "bidirectional"))
    )
    (net (code "27") (name "/PD1{slash}SDA{slash}D2") (class "Default")
      (node (ref "J5") (pin "3") (pinfunction "3_3") (pintype "bidirectional"))
      (node (ref "J9") (pin "9") (pinfunction "9_9") (pintype "bidirectional"))
      (node (ref "R13") (pin "1") (pinfunction "1_1") (pintype "passive"))
      (node (ref "U3") (pin "19") (pinfunction "PD1(SDA/INT1)_19") (pintype "bidirectional"))
    )
    (net (code "28") (name "/PD2{slash}RXI{slash}D0") (class "Default")
      (node (ref "J5") (pin "1") (pinfunction "1_1") (pintype "bidirectional"))
      (node (ref "R4") (pin "1") (pinfunction "1_1") (pintype "passive"))
      (node (ref "R_RX") (pin "1") (pinfunction "1_1") (pintype "passive"))
      (node (ref "U3") (pin "20") (pinfunction "PD2(RXD1/INT2)_20") (pintype "bidirectional"))
    )
    (net (code "29") (name "/PD3{slash}TXO{slash}D1") (class "Default")
      (node (ref "J5") (pin "2") (pinfunction "2_2") (pintype "bidirectional"))
      (node (ref "R9") (pin "1") (pinfunction "1_1") (pintype "passive"))
      (node (ref "R_TX") (pin "1") (pinfunction "1_1") (pintype "passive"))
      (node (ref "U3") (pin "21") (pinfunction "PD3(TXD1/INT3)_21") (pintype "bidirectional"))
    )
    (net (code "30") (name "/PD4{slash}A6{slash}D4") (class "Default")
      (node (ref "J5") (pin "5") (pinfunction "5_5") (pintype "bidirectional"))
      (node (ref "R41") (pin "1") (pinfunction "1_1") (pintype "passive"))
      (node (ref "U3") (pin "25") (pinfunction "PD4(ICP1/ADC8)_25") (pintype "bidirectional"))
    )
    (net (code "31") (name "/PD5{slash}TXLED") (class "Default")
      (node (ref "R53") (pin "1") (pinfunction "1_1") (pintype "passive"))
      (node (ref "U3") (pin "22") (pinfunction "PD5(XCLK1/~{CTS})_22") (pintype "bidirectional"))
    )
    (net (code "32") (name "/PD6{slash}A11{slash}D12") (class "Default")
      (node (ref "J9") (pin "5") (pinfunction "5_5") (pintype "bidirectional"))
      (node (ref "Q7") (pin "1") (pinfunction "B_1") (pintype "passive"))
      (node (ref "R32") (pin "1") (pinfunction "1_1") (pintype "passive"))
      (node (ref "R35") (pin "1") (pinfunction "1_1") (pintype "passive"))
      (node (ref "U3") (pin "26") (pinfunction "PD6(T1/ADC9/~{OC4D})_26") (pintype "bidirectional"))
    )
    (net (code "33") (name "/PD6{slash}D5") (class "Default")
      (node (ref "J5") (pin "6") (pinfunction "6_6") (pintype "bidirectional"))
      (node (ref "R42") (pin "1") (pinfunction "1_1") (pintype "passive"))
      (node (ref "U3") (pin "31") (pinfunction "PC6(OC3A/~{OC4A})_31") (pintype "bidirectional"))
    )
    (net (code "34") (name "/PD7{slash}A7{slash}D6") (class "Default")
      (node (ref "J5") (pin "7") (pinfunction "7_7") (pintype "bidirectional"))
      (node (ref "R16") (pin "2") (pinfunction "2_2") (pintype "passive"))
      (node (ref "U3") (pin "27") (pinfunction "PD7(T0/OC4D/ADC10)_27") (pintype "bidirectional"))
    )
    (net (code "35") (name "/PE6{slash}D7") (class "Default")
      (node (ref "J5") (pin "8") (pinfunction "8_8") (pintype "bidirectional"))
      (node (ref "R_D7") (pin "1") (pinfunction "1_1") (pintype "passive"))
      (node (ref "U3") (pin "1") (pinfunction "PE6(INT.6/AIN0)_1") (pintype "bidirectional"))
    )
    (net (code "36") (name "/PF0{slash}A5") (class "Default")
      (node (ref "J8") (pin "6") (pinfunction "6_6") (pintype "bidirectional"))
      (node (ref "U3") (pin "41") (pinfunction "PF0(ADC0)_41") (pintype "bidirectional"))
    )
    (net (code "37") (name "/PF1{slash}A4") (class "Default")
      (node (ref "J8") (pin "5") (pinfunction "5_5") (pintype "bidirectional"))
      (node (ref "U3") (pin "40") (pinfunction "PF1(ADC1)_40") (pintype "bidirectional"))
    )
    (net (code "38") (name "/PF4{slash}A3") (class "Default")
      (node (ref "J8") (pin "4") (pinfunction "4_4") (pintype "bidirectional"))
      (node (ref "U3") (pin "39") (pinfunction "PF4(ADC4/TCK)_39") (pintype "bidirectional"))
    )
    (net (code "39") (name "/PF5{slash}A2") (class "Default")
      (node (ref "J8") (pin "3") (pinfunction "3_3") (pintype "bidirectional"))
      (node (ref "U3") (pin "38") (pinfunction "PF5(ADC5/TMS)_38") (pintype "bidirectional"))
    )
    (net (code "40") (name "/PF6{slash}A1") (class "Default")
      (node (ref "J8") (pin "2") (pinfunction "2_2") (pintype "bidirectional"))
      (node (ref "U3") (pin "37") (pinfunction "PF6(ADC6/TDO)_37") (pintype "bidirectional"))
    )
    (net (code "41") (name "/PF7{slash}A0") (class "Default")
      (node (ref "J8") (pin "1") (pinfunction "1_1") (pintype "bidirectional"))
      (node (ref "U3") (pin "36") (pinfunction "PF7(ADC7/TDI)_36") (pintype "bidirectional"))
    )
    (net (code "42") (name "/SIMPRE") (class "Default")
      (node (ref "U5") (pin "54") (pinfunction "SIMPRE_54") (pintype "bidirectional"))
    )
    (net (code "43") (name "/SIM_ADC") (class "Default")
      (node (ref "U5") (pin "50") (pinfunction "ADC_50") (pintype "bidirectional"))
    )
    (net (code "44") (name "/SIM_CLK") (class "Default")
      (node (ref "R29") (pin "1") (pinfunction "1_1") (pintype "passive"))
      (node (ref "U5") (pin "55") (pinfunction "SIM_CLK_55") (pintype "bidirectional"))
    )
    (net (code "45") (name "/SIM_CTS") (class "Default")
      (node (ref "J13") (pin "4") (pinfunction "P$4_4") (pintype "bidirectional"))
      (node (ref "U5") (pin "34") (pinfunction "UART1_CTS_34") (pintype "bidirectional"))
    )
    (net (code "46") (name "/SIM_DATA") (class "Default")
      (node (ref "C40") (pin "2") (pinfunction "2_2") (pintype "passive"))
      (node (ref "R28") (pin "2") (pinfunction "2_2") (pintype "passive"))
      (node (ref "U5") (pin "14") (pinfunction "SIM_DATA_14") (pintype "bidirectional"))
    )
    (net (code "47") (name "/SIM_DCD") (class "Default")
      (node (ref "J11") (pin "4") (pinfunction "P$4_4") (pintype "bidirectional"))
      (node (ref "U5") (pin "70") (pinfunction "UART1_DCD_70") (pintype "bidirectional"))
    )
    (net (code "48") (name "/SIM_DTR") (class "Default")
      (node (ref "J11") (pin "3") (pinfunction "P$3_3") (pintype "bidirectional"))
      (node (ref "R56") (pin "2") (pinfunction "2_2") (pintype "passive"))
      (node (ref "R57") (pin "1") (pinfunction "1_1") (pintype "passive"))
      (node (ref "U5") (pin "69") (pinfunction "UART1_DTR_69") (pintype "bidirectional"))
    )
    (net (code "49") (name "/SIM_GPIO1") (class "Default")
      (node (ref "U5") (pin "3") (pinfunction "GPIO1_3") (pintype "bidirectional"))
    )
    (net (code "50") (name "/SIM_GPIO2") (class "Default")
      (node (ref "U5") (pin "27") (pinfunction "GPIO2_27") (pintype "bidirectional"))
    )
    (net (code "51") (name "/SIM_GPIO3") (class "Default")
      (node (ref "U5") (pin "28") (pinfunction "GPIO3_28") (pintype "bidirectional"))
    )
    (net (code "52") (name "/SIM_ISINK0") (class "Default")
      (node (ref "U5") (pin "47") (pinfunction "ISINK0_47") (pintype "bidirectional"))
    )
    (net (code "53") (name "/SIM_ISINK1") (class "Default")
      (node (ref "U5") (pin "46") (pinfunction "ISINK1_46") (pintype "bidirectional"))
    )
    (net (code "54") (name "/SIM_PWM") (class "Default")
      (node (ref "J11") (pin "1") (pinfunction "P$1_1") (pintype "bidirectional"))
      (node (ref "U5") (pin "26") (pinfunction "PWM_26") (pintype "bidirectional"))
    )
    (net (code "55") (name "/SIM_RI") (class "Default")
      (node (ref "J11") (pin "2") (pinfunction "P$2_2") (pintype "bidirectional"))
      (node (ref "U5") (pin "68") (pinfunction "UART1_RI_68") (pintype "bidirectional"))
    )
    (net (code "56") (name "/SIM_RST") (class "Default")
      (node (ref "R30") (pin "1") (pinfunction "1_1") (pintype "passive"))
      (node (ref "U5") (pin "15") (pinfunction "SIM_RST_15") (pintype "bidirectional"))
    )
    (net (code "57") (name "/SIM_RTS") (class "Default")
      (node (ref "J13") (pin "3") (pinfunction "P$3_3") (pintype "bidirectional"))
      (node (ref "U5") (pin "33") (pinfunction "UART1_RTS_33") (pintype "bidirectional"))
    )
    (net (code "58") (name "/SIM_RXD") (class "Default")
      (node (ref "J13") (pin "1") (pinfunction "P$1_1") (pintype "bidirectional"))
      (node (ref "Q5") (pin "2") (pinfunction "S_2") (pintype "passive"))
      (node (ref "R25") (pin "4") (pinfunction "1_4") (pintype "passive"))
      (node (ref "U5") (pin "31") (pinfunction "UART1_RXD_31") (pintype "bidirectional"))
    )
    (net (code "59") (name "/SIM_TXD") (class "Default")
      (node (ref "J13") (pin "2") (pinfunction "P$2_2") (pintype "bidirectional"))
      (node (ref "Q3") (pin "2") (pinfunction "S_2") (pintype "passive"))
      (node (ref "R25") (pin "6") (pinfunction "2_6") (pintype "passive"))
      (node (ref "U5") (pin "32") (pinfunction "UART1_TXD_32") (pintype "bidirectional"))
    )
    (net (code "60") (name "/SIM_VBAT") (class "Default")
      (node (ref "C102") (pin "+") (pinfunction "+_+") (pintype "passive"))
      (node (ref "C44") (pin "2") (pinfunction "2_2") (pintype "passive"))
      (node (ref "C46") (pin "2") (pinfunction "2_2") (pintype "passive"))
      (node (ref "C47") (pin "2") (pinfunction "2_2") (pintype "passive"))
      (node (ref "C8") (pin "2") (pinfunction "2_2") (pintype "passive"))
      (node (ref "L7") (pin "2") (pinfunction "2_2") (pintype "passive"))
      (node (ref "NET") (pin "+") (pinfunction "+_+") (pintype "passive"))
      (node (ref "PWR2") (pin "+") (pinfunction "+_+") (pintype "passive"))
      (node (ref "R51") (pin "1") (pinfunction "1_1") (pintype "passive"))
      (node (ref "STA") (pin "+") (pinfunction "+_+") (pintype "passive"))
      (node (ref "T_VBAT") (pin "T") (pinfunction "T_T") (pintype "bidirectional"))
      (node (ref "U5") (pin "1") (pinfunction "VBAT_1") (pintype "bidirectional"))
      (node (ref "U5") (pin "42") (pinfunction "VBAT_42") (pintype "bidirectional"))
    )
    (net (code "61") (name "/SIM_VRTC") (class "Default")
      (node (ref "C1") (pin "2") (pinfunction "2_2") (pintype "passive"))
      (node (ref "J1") (pin "+") (pinfunction "V+_+") (pintype "bidirectional"))
      (node (ref "U5") (pin "56") (pinfunction "VRTC_56") (pintype "bidirectional"))
    )
    (net (code "62") (name "/SIM_VSIM") (class "Default")
      (node (ref "C41") (pin "2") (pinfunction "2_2") (pintype "passive"))
      (node (ref "SIM1") (pin "1") (pinfunction "VCC_1") (pintype "bidirectional"))
      (node (ref "U5") (pin "16") (pinfunction "VSIM_16") (pintype "bidirectional"))
      (node (ref "U7") (pin "5") (pinfunction "5_5") (pintype "bidirectional"))
    )
    (net (code "63") (name "/SPK_N") (class "Default")
      (node (ref "C15") (pin "2") (pinfunction "2_2") (pintype "passive"))
      (node (ref "C16") (pin "2") (pinfunction "2_2") (pintype "passive"))
      (node (ref "C21") (pin "1") (pinfunction "1_1") (pintype "passive"))
      (node (ref "C22") (pin "1") (pinfunction "1_1") (pintype "passive"))
      (node (ref "L2") (pin "1") (pinfunction "1_1") (pintype "passive"))
      (node (ref "U5") (pin "13") (pinfunction "SPK1N_13") (pintype "bidirectional"))
    )
    (net (code "64") (name "/SPK_P") (class "Default")
      (node (ref "C21") (pin "2") (pinfunction "2_2") (pintype "passive"))
      (node (ref "C22") (pin "2") (pinfunction "2_2") (pintype "passive"))
      (node (ref "C23") (pin "1") (pinfunction "1_1") (pintype "passive"))
      (node (ref "C24") (pin "1") (pinfunction "1_1") (pintype "passive"))
      (node (ref "L3") (pin "1") (pinfunction "1_1") (pintype "passive"))
      (node (ref "U5") (pin "53") (pinfunction "SPK1P_53") (pintype "bidirectional"))
    )
    (net (code "65") (name "/STATUS") (class "Default")
      (node (ref "R32") (pin "2") (pinfunction "2_2") (pintype "passive"))
      (node (ref "U5") (pin "4") (pinfunction "STATUS_4") (pintype "bidirectional"))
    )
    (net (code "66") (name "/U5V") (class "Default")
      (node (ref "C33") (pin "1") (pinfunction "1_1") (pintype "passive"))
      (node (ref "C34") (pin "1") (pinfunction "1_1") (pintype "passive"))
      (node (ref "F2") (pin "1") (pinfunction "1_1") (pintype "bidirectional"))
      (node (ref "J4") (pin "1") (pinfunction "VCC_1") (pintype "bidirectional"))
      (node (ref "U3") (pin "2") (pinfunction "UVCC_2") (pintype "bidirectional"))
      (node (ref "U3") (pin "7") (pinfunction "VBUS_7") (pintype "bidirectional"))
    )
    (net (code "67") (name "/UCAP") (class "Default")
      (node (ref "C4") (pin "2") (pinfunction "2_2") (pintype "passive"))
      (node (ref "R47") (pin "2") (pinfunction "2_2") (pintype "passive"))
      (node (ref "U3") (pin "6") (pinfunction "UCAP_6") (pintype "bidirectional"))
    )
    (net (code "68") (name "/USB_D+") (class "Default")
      (node (ref "D13") (pin "2") (pinfunction "2_2") (pintype "bidirectional"))
      (node (ref "J4") (pin "3") (pinfunction "DP_3") (pintype "bidirectional"))
      (node (ref "R22") (pin "1") (pinfunction "1_1") (pintype "passive"))
      (node (ref "R37") (pin "2") (pinfunction "2_2") (pintype "passive"))
    )
    (net (code "69") (name "/USB_D-") (class "Default")
      (node (ref "D13") (pin "1") (pinfunction "1_1") (pintype "bidirectional"))
      (node (ref "J4") (pin "2") (pinfunction "DM_2") (pintype "bidirectional"))
      (node (ref "R33") (pin "1") (pinfunction "1_1") (pintype "passive"))
      (node (ref "R36") (pin "2") (pinfunction "2_2") (pintype "passive"))
    )
    (net (code "70") (name "/VCC") (class "Default")
      (node (ref "C49") (pin "2") (pinfunction "2_2") (pintype "passive"))
      (node (ref "C50") (pin "2") (pinfunction "2_2") (pintype "passive"))
      (node (ref "C51") (pin "2") (pinfunction "2_2") (pintype "passive"))
      (node (ref "C52") (pin "2") (pinfunction "2_2") (pintype "passive"))
      (node (ref "ICSP") (pin "6") (pinfunction "6_6") (pintype "bidirectional"))
      (node (ref "J7") (pin "7") (pinfunction "7_7") (pintype "bidirectional"))
      (node (ref "R11") (pin "1") (pinfunction "1_1") (pintype "passive"))
      (node (ref "R15") (pin "1") (pinfunction "1_1") (pintype "passive"))
      (node (ref "R18") (pin "1") (pinfunction "1_1") (pintype "passive"))
      (node (ref "R25") (pin "7") (pinfunction "2_7") (pintype "passive"))
      (node (ref "R25") (pin "8") (pinfunction "2_8") (pintype "passive"))
      (node (ref "R48") (pin "1") (pinfunction "1_1") (pintype "passive"))
      (node (ref "RX") (pin "+") (pinfunction "+_+") (pintype "passive"))
      (node (ref "SW1") (pin "COM1") (pinfunction "COM1_COM1") (pintype "bidirectional"))
      (node (ref "SW1") (pin "COM2") (pinfunction "COM2_COM2") (pintype "bidirectional"))
      (node (ref "TX") (pin "+") (pinfunction "+_+") (pintype "passive"))
      (node (ref "U3") (pin "14") (pinfunction "VCC_14") (pintype "bidirectional"))
      (node (ref "U3") (pin "24") (pinfunction "AVCC_24") (pintype "bidirectional"))
      (node (ref "U3") (pin "34") (pinfunction "VCC_34") (pintype "bidirectional"))
      (node (ref "U3") (pin "44") (pinfunction "AVCC_44") (pintype "bidirectional"))
    )
    (net (code "71") (name "/VEXT") (class "Default")
      (node (ref "C2") (pin "2") (pinfunction "2_2") (pintype "passive"))
      (node (ref "D3") (pin "-") (pinfunction "-_-") (pintype "passive"))
      (node (ref "Q3") (pin "1") (pinfunction "G_1") (pintype "passive"))
      (node (ref "Q5") (pin "1") (pinfunction "G_1") (pintype "passive"))
      (node (ref "R1") (pin "1") (pinfunction "1_1") (pintype "passive"))
      (node (ref "R25") (pin "3") (pinfunction "1_3") (pintype "passive"))
      (node (ref "R25") (pin "5") (pinfunction "2_5") (pintype "passive"))
      (node (ref "T_2V8") (pin "T") (pinfunction "T_T") (pintype "bidirectional"))
    )
    (net (code "72") (name "/~{RESET}") (class "Default")
      (node (ref "D1") (pin "-") (pinfunction "-_-") (pintype "passive"))
      (node (ref "ICSP") (pin "3") (pinfunction "3_3") (pintype "bidirectional"))
      (node (ref "J7") (pin "6") (pinfunction "6_6") (pintype "bidirectional"))
      (node (ref "R48") (pin "2") (pinfunction "2_2") (pintype "passive"))
      (node (ref "RST") (pin "-") (pinfunction "-_-") (pintype "passive"))
      (node (ref "SW3") (pin "2") (pinfunction "2_2") (pintype "bidirectional"))
      (node (ref "U3") (pin "13") (pinfunction "~{RESET}_13") (pintype "bidirectional"))
    )
    (net (code "73") (name "/~{RES}") (class "Default")
      (node (ref "D1") (pin "+") (pinfunction "+_+") (pintype "passive"))
      (node (ref "R16") (pin "1") (pinfunction "1_1") (pintype "passive"))
      (node (ref "U5") (pin "49") (pinfunction "RESET_49") (pintype "bidirectional"))
    )
    (net (code "74") (name "DC_5V") (class "Default")
      (node (ref "C17") (pin "1") (pinfunction "1_1") (pintype "passive"))
      (node (ref "C37") (pin "+") (pinfunction "+_+") (pintype "passive"))
      (node (ref "C6") (pin "+") (pinfunction "+_+") (pintype "passive"))
      (node (ref "C7") (pin "1") (pinfunction "1_1") (pintype "passive"))
      (node (ref "J7") (pin "4") (pinfunction "4_4") (pintype "bidirectional"))
      (node (ref "Q8") (pin "1") (pinfunction "G_1") (pintype "passive"))
      (node (ref "Q9") (pin "2") (pinfunction "S_2") (pintype "passive"))
      (node (ref "R38") (pin "2") (pinfunction "2_2") (pintype "passive"))
      (node (ref "R44") (pin "2") (pinfunction "2_2") (pintype "passive"))
      (node (ref "R_USB") (pin "2") (pinfunction "2_2") (pintype "passive"))
      (node (ref "SW1") (pin "CH1A") (pinfunction "CH1A_CH1A") (pintype "bidirectional"))
      (node (ref "SW1") (pin "CH2A") (pinfunction "CH2A_CH2A") (pintype "bidirectional"))
      (node (ref "T_5V") (pin "T") (pinfunction "T_T") (pintype "bidirectional"))
      (node (ref "U1") (pin "2") (pinfunction "OUT_2") (pintype "bidirectional"))
      (node (ref "U10") (pin "8") (pinfunction "+V_8") (pintype "power_in"))
      (node (ref "U8") (pin "3") (pinfunction "IN_3") (pintype "bidirectional"))
    )
    (net (code "75") (name "GND_POWER") (class "Default")
      (node (ref "ANT2") (pin "GND1") (pinfunction "GND1_GND1") (pintype "bidirectional"))
      (node (ref "ANT2") (pin "GND2") (pinfunction "GND2_GND2") (pintype "bidirectional"))
      (node (ref "ANT2") (pin "GND3") (pinfunction "GND3_GND3") (pintype "bidirectional"))
      (node (ref "C1") (pin "1") (pinfunction "1_1") (pintype "passive"))
      (node (ref "C10") (pin "1") (pinfunction "1_1") (pintype "passive"))
      (node (ref "C102") (pin "-") (pinfunction "-_-") (pintype "passive"))
      (node (ref "C12") (pin "-") (pinfunction "-_-") (pintype "passive"))
      (node (ref "C15") (pin "1") (pinfunction "1_1") (pintype "passive"))
      (node (ref "C16") (pin "1") (pinfunction "1_1") (pintype "passive"))
      (node (ref "C17") (pin "2") (pinfunction "2_2") (pintype "passive"))
      (node (ref "C18") (pin "1") (pinfunction "1_1") (pintype "passive"))
      (node (ref "C2") (pin "1") (pinfunction "1_1") (pintype "passive"))
      (node (ref "C23") (pin "2") (pinfunction "2_2") (pintype "passive"))
      (node (ref "C24") (pin "2") (pinfunction "2_2") (pintype "passive"))
      (node (ref "C27") (pin "1") (pinfunction "1_1") (pintype "passive"))
      (node (ref "C28") (pin "1") (pinfunction "1_1") (pintype "passive"))
      (node (ref "C29") (pin "2") (pinfunction "2_2") (pintype "passive"))
      (node (ref "C3") (pin "1") (pinfunction "1_1") (pintype "passive"))
      (node (ref "C30") (pin "1") (pinfunction "1_1") (pintype "passive"))
      (node (ref "C31") (pin "1") (pinfunction "1_1") (pintype "passive"))
      (node (ref "C32") (pin "1") (pinfunction "1_1") (pintype "passive"))
      (node (ref "C33") (pin "2") (pinfunction "2_2") (pintype "passive"))
      (node (ref "C34") (pin "2") (pinfunction "2_2") (pintype "passive"))
      (node (ref "C36") (pin "-") (pinfunction "-_-") (pintype "passive"))
      (node (ref "C37") (pin "-") (pinfunction "-_-") (pintype "passive"))
      (node (ref "C38") (pin "-") (pinfunction "-_-") (pintype "passive"))
      (node (ref "C39") (pin "2") (pinfunction "2_2") (pintype "passive"))
      (node (ref "C4") (pin "1") (pinfunction "1_1") (pintype "passive"))
      (node (ref "C40") (pin "1") (pinfunction "1_1") (pintype "passive"))
      (node (ref "C41") (pin "1") (pinfunction "1_1") (pintype "passive"))
      (node (ref "C42") (pin "1") (pinfunction "1_1") (pintype "passive"))
      (node (ref "C44") (pin "1") (pinfunction "1_1") (pintype "passive"))
      (node (ref "C46") (pin "1") (pinfunction "1_1") (pintype "passive"))
      (node (ref "C47") (pin "1") (pinfunction "1_1") (pintype "passive"))
      (node (ref "C48") (pin "1") (pinfunction "1_1") (pintype "passive"))
      (node (ref "C49") (pin "1") (pinfunction "1_1") (pintype "passive"))
      (node (ref "C5") (pin "1") (pinfunction "1_1") (pintype "passive"))
      (node (ref "C50") (pin "1") (pinfunction "1_1") (pintype "passive"))
      (node (ref "C51") (pin "1") (pinfunction "1_1") (pintype "passive"))
      (node (ref "C52") (pin "1") (pinfunction "1_1") (pintype "passive"))
      (node (ref "C6") (pin "-") (pinfunction "-_-") (pintype "passive"))
      (node (ref "C7") (pin "2") (pinfunction "2_2") (pintype "passive"))
      (node (ref "D10") (pin "1") (pinfunction "1_1") (pintype "bidirectional"))
      (node (ref "D13") (pin "3") (pinfunction "3_3") (pintype "bidirectional"))
      (node (ref "D6") (pin "1") (pinfunction "1_1") (pintype "bidirectional"))
      (node (ref "D8") (pin "1") (pinfunction "1_1") (pintype "bidirectional"))
      (node (ref "D9") (pin "+") (pinfunction "+_+") (pintype "passive"))
      (node (ref "ICSP") (pin "4") (pinfunction "4_4") (pintype "bidirectional"))
      (node (ref "J1") (pin "-") (pinfunction "V-_-") (pintype "bidirectional"))
      (node (ref "J2") (pin "-") (pinfunction "-_-") (pintype "bidirectional"))
      (node (ref "J3") (pin "2") (pinfunction "2_2") (pintype "bidirectional"))
      (node (ref "J4") (pin "5") (pinfunction "GND_5") (pintype "bidirectional"))
      (node (ref "J4") (pin "S1") (pinfunction "GND_S1") (pintype "bidirectional"))
      (node (ref "J4") (pin "S2") (pinfunction "GND_S2") (pintype "bidirectional"))
      (node (ref "J4") (pin "S3") (pinfunction "GND_S3") (pintype "bidirectional"))
      (node (ref "J4") (pin "S4") (pinfunction "GND_S4") (pintype "bidirectional"))
      (node (ref "J4") (pin "S5") (pinfunction "GND_S5") (pintype "bidirectional"))
      (node (ref "J4") (pin "S6") (pinfunction "GND_S6") (pintype "bidirectional"))
      (node (ref "J7") (pin "2") (pinfunction "2_2") (pintype "bidirectional"))
      (node (ref "J7") (pin "3") (pinfunction "3_3") (pintype "bidirectional"))
      (node (ref "J9") (pin "7") (pinfunction "7_7") (pintype "bidirectional"))
      (node (ref "L1") (pin "-") (pinfunction "-_-") (pintype "passive"))
      (node (ref "PWR1") (pin "-") (pinfunction "-_-") (pintype "passive"))
      (node (ref "Q1") (pin "2") (pinfunction "E_2") (pintype "passive"))
      (node (ref "Q4") (pin "2") (pinfunction "S_2") (pintype "passive"))
      (node (ref "Q6") (pin "2") (pinfunction "E_2") (pintype "passive"))
      (node (ref "Q7") (pin "2") (pinfunction "E_2") (pintype "passive"))
      (node (ref "R23") (pin "1") (pinfunction "1_1") (pintype "passive"))
      (node (ref "R34") (pin "2") (pinfunction "2_2") (pintype "passive"))
      (node (ref "R35") (pin "2") (pinfunction "2_2") (pintype "passive"))
      (node (ref "R49") (pin "1") (pinfunction "1_1") (pintype "passive"))
      (node (ref "R52") (pin "2") (pinfunction "2_2") (pintype "passive"))
      (node (ref "R56") (pin "1") (pinfunction "1_1") (pintype "passive"))
      (node (ref "R6") (pin "1") (pinfunction "1_1") (pintype "passive"))
      (node (ref "R7") (pin "1") (pinfunction "1_1") (pintype "passive"))
      (node (ref "SIM1") (pin "6") (pinfunction "GND_6") (pintype "bidirectional"))
      (node (ref "SIM1") (pin "P1") (pinfunction "7_P1") (pintype "bidirectional"))
      (node (ref "SIM1") (pin "P2") (pinfunction "8_P2") (pintype "bidirectional"))
      (node (ref "SW3") (pin "1") (pinfunction "1_1") (pintype "bidirectional"))
      (node (ref "SW3") (pin "S1") (pinfunction "S1_S1") (pintype "bidirectional"))
      (node (ref "SW3") (pin "S2") (pinfunction "S2_S2") (pintype "bidirectional"))
      (node (ref "U1") (pin "3") (pinfunction "GND_3") (pintype "bidirectional"))
      (node (ref "U10") (pin "4") (pinfunction "GND_4") (pintype "power_in"))
      (node (ref "U3") (pin "15") (pinfunction "GND_15") (pintype "bidirectional"))
      (node (ref "U3") (pin "23") (pinfunction "GND_23") (pintype "bidirectional"))
      (node (ref "U3") (pin "33") (pinfunction "PE2(~{HWB})_33") (pintype "bidirectional"))
      (node (ref "U3") (pin "35") (pinfunction "GND_35") (pintype "bidirectional"))
      (node (ref "U3") (pin "43") (pinfunction "GND_43") (pintype "bidirectional"))
      (node (ref "U3") (pin "5") (pinfunction "UGND_5") (pintype "bidirectional"))
      (node (ref "U3") (pin "TAB") (pinfunction "GND_TAB") (pintype "bidirectional"))
      (node (ref "U5") (pin "12") (pinfunction "MIC1N_12") (pintype "bidirectional"))
      (node (ref "U5") (pin "2") (pinfunction "GND_2") (pintype "bidirectional"))
      (node (ref "U5") (pin "35") (pinfunction "GND_35") (pintype "bidirectional"))
      (node (ref "U5") (pin "37") (pinfunction "GND_37") (pintype "bidirectional"))
      (node (ref "U5") (pin "38") (pinfunction "GND_38") (pintype "bidirectional"))
      (node (ref "U5") (pin "39") (pinfunction "GND_39") (pintype "bidirectional"))
      (node (ref "U5") (pin "41") (pinfunction "GND_41") (pintype "bidirectional"))
      (node (ref "U5") (pin "43") (pinfunction "GND_43") (pintype "bidirectional"))
      (node (ref "U5") (pin "44") (pinfunction "GND_44") (pintype "bidirectional"))
      (node (ref "U5") (pin "45") (pinfunction "GND_45") (pintype "bidirectional"))
      (node (ref "U5") (pin "58") (pinfunction "GND_58") (pintype "bidirectional"))
      (node (ref "U5") (pin "6") (pinfunction "GND_6") (pintype "bidirectional"))
      (node (ref "U5") (pin "67") (pinfunction "GND_67") (pintype "bidirectional"))
      (node (ref "U5") (pin "71") (pinfunction "GND_71") (pintype "bidirectional"))
      (node (ref "U5") (pin "72") (pinfunction "GND_72") (pintype "bidirectional"))
      (node (ref "U5") (pin "73") (pinfunction "GND_73") (pintype "bidirectional"))
      (node (ref "U5") (pin "76") (pinfunction "GND_76") (pintype "bidirectional"))
      (node (ref "U5") (pin "77") (pinfunction "GND_77") (pintype "bidirectional"))
      (node (ref "U5") (pin "78") (pinfunction "GND_78") (pintype "bidirectional"))
      (node (ref "U5") (pin "79") (pinfunction "GND_79") (pintype "bidirectional"))
      (node (ref "U5") (pin "8") (pinfunction "GND_8") (pintype "bidirectional"))
      (node (ref "U5") (pin "80") (pinfunction "GND_80") (pintype "bidirectional"))
      (node (ref "U5") (pin "81") (pinfunction "GND_81") (pintype "bidirectional"))
      (node (ref "U5") (pin "82") (pinfunction "GND_82") (pintype "bidirectional"))
      (node (ref "U5") (pin "83") (pinfunction "GND_83") (pintype "bidirectional"))
      (node (ref "U5") (pin "84") (pinfunction "GND_84") (pintype "bidirectional"))
      (node (ref "U5") (pin "85") (pinfunction "GND_85") (pintype "bidirectional"))
      (node (ref "U5") (pin "86") (pinfunction "GND_86") (pintype "bidirectional"))
      (node (ref "U5") (pin "87") (pinfunction "GND_87") (pintype "bidirectional"))
      (node (ref "U5") (pin "88") (pinfunction "GND_88") (pintype "bidirectional"))
      (node (ref "U6") (pin "4") (pinfunction "GND_4") (pintype "power_in"))
      (node (ref "U7") (pin "2") (pinfunction "2_2") (pintype "bidirectional"))
      (node (ref "U8") (pin "1") (pinfunction "GND_1") (pintype "bidirectional"))
    )
    (net (code "76") (name "Net-(ANT2-PadD)") (class "Default")
      (node (ref "ANT2") (pin "D") (pinfunction "D_D") (pintype "bidirectional"))
      (node (ref "C31") (pin "2") (pinfunction "2_2") (pintype "passive"))
      (node (ref "R24") (pin "1") (pinfunction "1_1") (pintype "passive"))
    )
    (net (code "77") (name "Net-(BT_ANT-Pad1)") (class "Default")
      (node (ref "BT_ANT") (pin "1") (pinfunction "1_1") (pintype "bidirectional"))
      (node (ref "C27") (pin "2") (pinfunction "2_2") (pintype "passive"))
      (node (ref "L21") (pin "1") (pinfunction "1_1") (pintype "passive"))
    )
    (net (code "78") (name "Net-(C9-Pad2)") (class "Default")
      (node (ref "C9") (pin "2") (pinfunction "2_2") (pintype "passive"))
      (node (ref "L6") (pin "1") (pinfunction "1_1") (pintype "passive"))
    )
    (net (code "79") (name "Net-(C11-Pad2)") (class "Default")
      (node (ref "C11") (pin "2") (pinfunction "2_2") (pintype "passive"))
      (node (ref "L8") (pin "1") (pinfunction "1_1") (pintype "passive"))
    )
    (net (code "80") (name "Net-(C30-Pad2)") (class "Default")
      (node (ref "C30") (pin "2") (pinfunction "2_2") (pintype "passive"))
      (node (ref "L5") (pin "1") (pinfunction "1_1") (pintype "passive"))
      (node (ref "R19") (pin "2") (pinfunction "2_2") (pintype "passive"))
    )
    (net (code "81") (name "Net-(D2-+)") (class "Default")
      (node (ref "D2") (pin "2") (pinfunction "+_2") (pintype "passive"))
      (node (ref "F2") (pin "2") (pinfunction "2_2") (pintype "bidirectional"))
      (node (ref "Q2") (pin "3") (pinfunction "D_3") (pintype "passive"))
      (node (ref "Q9") (pin "3") (pinfunction "D_3") (pintype "passive"))
      (node (ref "T_USB") (pin "T") (pinfunction "T_T") (pintype "bidirectional"))
    )
    (net (code "82") (name "Net-(D2--)") (class "Default")
      (node (ref "C36") (pin "+") (pinfunction "+_+") (pintype "passive"))
      (node (ref "C48") (pin "2") (pinfunction "2_2") (pintype "passive"))
      (node (ref "D2") (pin "1") (pinfunction "-_1") (pintype "passive"))
      (node (ref "D5") (pin "1") (pinfunction "-_1") (pintype "passive"))
      (node (ref "Q2") (pin "2") (pinfunction "S_2") (pintype "passive"))
      (node (ref "R43") (pin "2") (pinfunction "2_2") (pintype "passive"))
      (node (ref "R50") (pin "2") (pinfunction "2_2") (pintype "passive"))
      (node (ref "U6") (pin "2") (pinfunction "VIN_2") (pintype "input"))
    )
    (net (code "83") (name "Net-(D4-Pad-)") (class "Default")
      (node (ref "D4") (pin "-") (pinfunction "-_-") (pintype "passive"))
      (node (ref "R57") (pin "2") (pinfunction "2_2") (pintype "passive"))
    )
    (net (code "84") (name "Net-(D8-Pad2)") (class "Default")
      (node (ref "D8") (pin "2") (pinfunction "2_2") (pintype "bidirectional"))
      (node (ref "J3") (pin "1") (pinfunction "1_1") (pintype "bidirectional"))
      (node (ref "L5") (pin "2") (pinfunction "2_2") (pintype "passive"))
    )
    (net (code "85") (name "Net-(D11-+)") (class "Default")
      (node (ref "D11") (pin "2") (pinfunction "+_2") (pintype "passive"))
      (node (ref "D5") (pin "2") (pinfunction "+_2") (pintype "passive"))
      (node (ref "J2") (pin "+") (pinfunction "+_+") (pintype "bidirectional"))
      (node (ref "R6") (pin "2") (pinfunction "2_2") (pintype "passive"))
      (node (ref "R8") (pin "2") (pinfunction "2_2") (pintype "passive"))
    )
    (net (code "86") (name "Net-(J3-Pad6)") (class "Default")
      (node (ref "J3") (pin "6") (pinfunction "6_6") (pintype "bidirectional"))
      (node (ref "R12") (pin "1") (pinfunction "1_1") (pintype "passive"))
      (node (ref "R15") (pin "2") (pinfunction "2_2") (pintype "passive"))
    )
    (net (code "87") (name "Net-(L1-Pad+)") (class "Default")
      (node (ref "L1") (pin "+") (pinfunction "+_+") (pintype "passive"))
      (node (ref "R55") (pin "1") (pinfunction "1_1") (pintype "passive"))
    )
    (net (code "88") (name "Net-(NET-Pad-)") (class "Default")
      (node (ref "NET") (pin "-") (pinfunction "-_-") (pintype "passive"))
      (node (ref "R26") (pin "1") (pinfunction "1_1") (pintype "passive"))
    )
    (net (code "89") (name "Net-(PWR1-Pad+)") (class "Default")
      (node (ref "PWR1") (pin "+") (pinfunction "+_+") (pintype "passive"))
      (node (ref "R18") (pin "2") (pinfunction "2_2") (pintype "passive"))
    )
    (net (code "90") (name "Net-(PWR2-Pad-)") (class "Default")
      (node (ref "PWR2") (pin "-") (pinfunction "-_-") (pintype "passive"))
      (node (ref "R49") (pin "2") (pinfunction "2_2") (pintype "passive"))
    )
    (net (code "91") (name "Net-(Q1-B)") (class "Default")
      (node (ref "Q1") (pin "1") (pinfunction "B_1") (pintype "passive"))
      (node (ref "R3") (pin "2") (pinfunction "2_2") (pintype "passive"))
      (node (ref "R7") (pin "2") (pinfunction "2_2") (pintype "passive"))
    )
    (net (code "92") (name "Net-(Q1-C)") (class "Default")
      (node (ref "Q1") (pin "3") (pinfunction "C_3") (pintype "passive"))
      (node (ref "U5") (pin "48") (pinfunction "PWRKEY_48") (pintype "bidirectional"))
    )
    (net (code "93") (name "Net-(Q2-G)") (class "Default")
      (node (ref "Q2") (pin "1") (pinfunction "G_1") (pintype "passive"))
      (node (ref "Q8") (pin "3") (pinfunction "D_3") (pintype "passive"))
      (node (ref "R43") (pin "1") (pinfunction "1_1") (pintype "passive"))
    )
    (net (code "94") (name "Net-(Q4-G)") (class "Default")
      (node (ref "Q4") (pin "1") (pinfunction "G_1") (pintype "passive"))
      (node (ref "R45") (pin "1") (pinfunction "1_1") (pintype "passive"))
    )
    (net (code "95") (name "Net-(Q6-B)") (class "Default")
      (node (ref "Q6") (pin "1") (pinfunction "B_1") (pintype "passive"))
      (node (ref "R31") (pin "1") (pinfunction "1_1") (pintype "passive"))
      (node (ref "R34") (pin "1") (pinfunction "1_1") (pintype "passive"))
    )
    (net (code "96") (name "Net-(Q6-C)") (class "Default")
      (node (ref "Q6") (pin "3") (pinfunction "C_3") (pintype "passive"))
      (node (ref "R26") (pin "2") (pinfunction "2_2") (pintype "passive"))
    )
    (net (code "97") (name "Net-(Q7-C)") (class "Default")
      (node (ref "Q7") (pin "3") (pinfunction "C_3") (pintype "passive"))
      (node (ref "R27") (pin "2") (pinfunction "2_2") (pintype "passive"))
    )
    (net (code "98") (name "Net-(R11-Pad2)") (class "Default")
      (node (ref "R11") (pin "2") (pinfunction "2_2") (pintype "passive"))
      (node (ref "RST") (pin "+") (pinfunction "+_+") (pintype "passive"))
    )
    (net (code "99") (name "Net-(R27-Pad1)") (class "Default")
      (node (ref "R27") (pin "1") (pinfunction "1_1") (pintype "passive"))
      (node (ref "STA") (pin "-") (pinfunction "-_-") (pintype "passive"))
    )
    (net (code "100") (name "Net-(R53-Pad2)") (class "Default")
      (node (ref "R53") (pin "2") (pinfunction "2_2") (pintype "passive"))
      (node (ref "TX") (pin "-") (pinfunction "-_-") (pintype "passive"))
    )
    (net (code "101") (name "Net-(R54-Pad2)") (class "Default")
      (node (ref "R54") (pin "2") (pinfunction "2_2") (pintype "passive"))
      (node (ref "RX") (pin "-") (pinfunction "-_-") (pintype "passive"))
    )
    (net (code "102") (name "Net-(SIM1-CLK)") (class "Default")
      (node (ref "R29") (pin "2") (pinfunction "2_2") (pintype "passive"))
      (node (ref "SIM1") (pin "3") (pinfunction "CLK_3") (pintype "bidirectional"))
      (node (ref "U7") (pin "3") (pinfunction "3_3") (pintype "bidirectional"))
    )
    (net (code "103") (name "Net-(SIM1-I{slash}O)") (class "Default")
      (node (ref "R28") (pin "1") (pinfunction "1_1") (pintype "passive"))
      (node (ref "SIM1") (pin "4") (pinfunction "I/O_4") (pintype "bidirectional"))
      (node (ref "U7") (pin "4") (pinfunction "4_4") (pintype "bidirectional"))
    )
    (net (code "104") (name "Net-(SIM1-RST)") (class "Default")
      (node (ref "R30") (pin "2") (pinfunction "2_2") (pintype "passive"))
      (node (ref "SIM1") (pin "2") (pinfunction "RST_2") (pintype "bidirectional"))
      (node (ref "U7") (pin "1") (pinfunction "1_1") (pintype "bidirectional"))
    )
    (net (code "105") (name "Net-(U3-XTAL1)") (class "Default")
      (node (ref "C5") (pin "2") (pinfunction "2_2") (pintype "passive"))
      (node (ref "U3") (pin "17") (pinfunction "XTAL1_17") (pintype "bidirectional"))
      (node (ref "X1") (pin "2") (pinfunction "2_2") (pintype "passive"))
    )
    (net (code "106") (name "Net-(U3-XTAL2)") (class "Default")
      (node (ref "C18") (pin "2") (pinfunction "2_2") (pintype "passive"))
      (node (ref "U3") (pin "16") (pinfunction "XTAL2_16") (pintype "bidirectional"))
      (node (ref "X1") (pin "1") (pinfunction "1_1") (pintype "passive"))
    )
    (net (code "107") (name "Net-(U5-COL0)") (class "Default")
      (node (ref "R40") (pin "2") (pinfunction "2_2") (pintype "passive"))
      (node (ref "U5") (pin "20") (pinfunction "COL0_20") (pintype "bidirectional"))
    )
    (net (code "108") (name "Net-(U5-COL1)") (class "Default")
      (node (ref "R41") (pin "2") (pinfunction "2_2") (pintype "passive"))
      (node (ref "U5") (pin "25") (pinfunction "COL1_25") (pintype "bidirectional"))
    )
    (net (code "109") (name "Net-(U5-COL2)") (class "Default")
      (node (ref "R42") (pin "2") (pinfunction "2_2") (pintype "passive"))
      (node (ref "U5") (pin "22") (pinfunction "COL2_22") (pintype "bidirectional"))
    )
    (net (code "110") (name "Net-(U5-ROW0)") (class "Default")
      (node (ref "R4") (pin "2") (pinfunction "2_2") (pintype "passive"))
      (node (ref "U5") (pin "62") (pinfunction "ROW0_62") (pintype "bidirectional"))
    )
    (net (code "111") (name "Net-(U5-ROW1)") (class "Default")
      (node (ref "R9") (pin "2") (pinfunction "2_2") (pintype "passive"))
      (node (ref "U5") (pin "60") (pinfunction "ROW1_60") (pintype "bidirectional"))
    )
    (net (code "112") (name "Net-(U5-ROW2)") (class "Default")
      (node (ref "R13") (pin "2") (pinfunction "2_2") (pintype "passive"))
      (node (ref "U5") (pin "61") (pinfunction "ROW2_61") (pintype "bidirectional"))
    )
    (net (code "113") (name "Net-(U5-USB_DM)") (class "Default")
      (node (ref "R36") (pin "1") (pinfunction "1_1") (pintype "passive"))
      (node (ref "U5") (pin "19") (pinfunction "USB_DM_19") (pintype "bidirectional"))
    )
    (net (code "114") (name "Net-(U5-USB_DP)") (class "Default")
      (node (ref "R37") (pin "1") (pinfunction "1_1") (pintype "passive"))
      (node (ref "U5") (pin "59") (pinfunction "USB_DP_59") (pintype "bidirectional"))
    )
    (net (code "115") (name "Net-(U5-VBUS)") (class "Default")
      (node (ref "C42") (pin "2") (pinfunction "2_2") (pintype "passive"))
      (node (ref "R_USB") (pin "1") (pinfunction "1_1") (pintype "passive"))
      (node (ref "U5") (pin "7") (pinfunction "VBUS_7") (pintype "bidirectional"))
    )
    (net (code "116") (name "Net-(U5-VEXT)") (class "Default")
      (node (ref "R1") (pin "2") (pinfunction "2_2") (pintype "passive"))
      (node (ref "U5") (pin "18") (pinfunction "VEXT_18") (pintype "bidirectional"))
    )
    (net (code "117") (name "Net-(U6-EN)") (class "Default")
      (node (ref "R50") (pin "1") (pinfunction "1_1") (pintype "passive"))
      (node (ref "U6") (pin "7") (pinfunction "EN_7") (pintype "input"))
    )
    (net (code "118") (name "Net-(U6-FB)") (class "Default")
      (node (ref "C8") (pin "1") (pinfunction "1_1") (pintype "passive"))
      (node (ref "R51") (pin "2") (pinfunction "2_2") (pintype "passive"))
      (node (ref "R52") (pin "1") (pinfunction "1_1") (pintype "passive"))
      (node (ref "U6") (pin "5") (pinfunction "FB_5") (pintype "input"))
    )
    (net (code "119") (name "Net-(U6-SW)") (class "Default")
      (node (ref "D9") (pin "-") (pinfunction "-_-") (pintype "passive"))
      (node (ref "L7") (pin "1") (pinfunction "1_1") (pintype "passive"))
      (node (ref "U6") (pin "3") (pinfunction "SW_3") (pintype "output"))
    )
    (net (code "120") (name "Net-(U10A--IN1)") (class "Default")
      (node (ref "R23") (pin "2") (pinfunction "2_2") (pintype "passive"))
      (node (ref "R39") (pin "1") (pinfunction "1_1") (pintype "passive"))
      (node (ref "U10") (pin "2") (pinfunction "-IN1_2") (pintype "input"))
    )
    (net (code "121") (name "Net-(U10A-OUT1)") (class "Default")
      (node (ref "R45") (pin "2") (pinfunction "2_2") (pintype "passive"))
      (node (ref "U10") (pin "1") (pinfunction "OUT1_1") (pintype "output"))
    )
    (net (code "122") (name "unconnected-(BT_ANT-Pad2)") (class "Default")
      (node (ref "BT_ANT") (pin "2") (pinfunction "2_2") (pintype "bidirectional"))
    )
    (net (code "123") (name "unconnected-(J2-PadCDN)") (class "Default")
      (node (ref "J2") (pin "CDN") (pinfunction "CDN_CDN") (pintype "bidirectional"))
    )
    (net (code "124") (name "unconnected-(J3-Pad5)") (class "Default")
      (node (ref "J3") (pin "5") (pinfunction "5_5") (pintype "bidirectional"))
    )
    (net (code "125") (name "unconnected-(J3-Pad7)") (class "Default")
      (node (ref "J3") (pin "7") (pinfunction "7_7") (pintype "bidirectional"))
    )
    (net (code "126") (name "unconnected-(J3-Pad8)") (class "Default")
      (node (ref "J3") (pin "8") (pinfunction "8_8") (pintype "bidirectional"))
    )
    (net (code "127") (name "unconnected-(J4-ID-Pad4)") (class "Default")
      (node (ref "J4") (pin "4") (pinfunction "ID_4") (pintype "bidirectional"))
    )
    (net (code "128") (name "unconnected-(J7-Pad8)") (class "Default")
      (node (ref "J7") (pin "8") (pinfunction "8_8") (pintype "bidirectional"))
    )
    (net (code "129") (name "unconnected-(SIM1-VPP-Pad5)") (class "Default")
      (node (ref "SIM1") (pin "5") (pinfunction "VPP_5") (pintype "bidirectional"))
    )
    (net (code "130") (name "unconnected-(U5-BPI_BUS1-Pad5)") (class "Default")
      (node (ref "U5") (pin "5") (pinfunction "BPI_BUS1_5") (pintype "bidirectional"))
    )
    (net (code "131") (name "unconnected-(U5-COL3-Pad21)") (class "Default")
      (node (ref "U5") (pin "21") (pinfunction "COL3_21") (pintype "bidirectional"))
    )
    (net (code "132") (name "unconnected-(U5-COL4-Pad24)") (class "Default")
      (node (ref "U5") (pin "24") (pinfunction "COL4_24") (pintype "bidirectional"))
    )
    (net (code "133") (name "unconnected-(U5-MIC2N-Pad10)") (class "Default")
      (node (ref "U5") (pin "10") (pinfunction "MIC2N_10") (pintype "bidirectional"))
    )
    (net (code "134") (name "unconnected-(U5-MIC2P-Pad9)") (class "Default")
      (node (ref "U5") (pin "9") (pinfunction "MIC2P_9") (pintype "bidirectional"))
    )
    (net (code "135") (name "unconnected-(U5-PCMCLK-Pad29)") (class "Default")
      (node (ref "U5") (pin "29") (pinfunction "PCMCLK_29") (pintype "bidirectional"))
    )
    (net (code "136") (name "unconnected-(U5-PCMIN-Pad66)") (class "Default")
      (node (ref "U5") (pin "66") (pinfunction "PCMIN_66") (pintype "bidirectional"))
    )
    (net (code "137") (name "unconnected-(U5-PCMOUT-Pad30)") (class "Default")
      (node (ref "U5") (pin "30") (pinfunction "PCMOUT_30") (pintype "bidirectional"))
    )
    (net (code "138") (name "unconnected-(U5-PCMSYNC-Pad65)") (class "Default")
      (node (ref "U5") (pin "65") (pinfunction "PCMSYNC_65") (pintype "bidirectional"))
    )
    (net (code "139") (name "unconnected-(U5-ROW3-Pad23)") (class "Default")
      (node (ref "U5") (pin "23") (pinfunction "ROW3_23") (pintype "bidirectional"))
    )
    (net (code "140") (name "unconnected-(U5-ROW4-Pad63)") (class "Default")
      (node (ref "U5") (pin "63") (pinfunction "ROW4_63") (pintype "bidirectional"))
    )
    (net (code "141") (name "unconnected-(U5-SCL-Pad74)") (class "Default")
      (node (ref "U5") (pin "74") (pinfunction "SCL_74") (pintype "bidirectional"))
    )
    (net (code "142") (name "unconnected-(U5-SDA-Pad75)") (class "Default")
      (node (ref "U5") (pin "75") (pinfunction "SDA_75") (pintype "bidirectional"))
    )
    (net (code "143") (name "unconnected-(U5-SPK2N-Pad11)") (class "Default")
      (node (ref "U5") (pin "11") (pinfunction "SPK2N_11") (pintype "bidirectional"))
    )
    (net (code "144") (name "unconnected-(U5-SPK2P-Pad51)") (class "Default")
      (node (ref "U5") (pin "51") (pinfunction "SPK2P_51") (pintype "bidirectional"))
    )
    (net (code "145") (name "unconnected-(U6-NC-Pad1)") (class "Default")
      (node (ref "U6") (pin "1") (pinfunction "NC_1") (pintype "no_connect"))
    )
    (net (code "146") (name "unconnected-(U6-NC-Pad6)") (class "Default")
      (node (ref "U6") (pin "6") (pinfunction "NC_6") (pintype "no_connect"))
    )
    (net (code "147") (name "unconnected-(U6-NC-Pad8)") (class "Default")
      (node (ref "U6") (pin "8") (pinfunction "NC_8") (pintype "no_connect"))
    )
  )
)
